# SCH-HC15C_REV2_PG3.net
KiCad netlist of a schematic drawn in Altium Designer
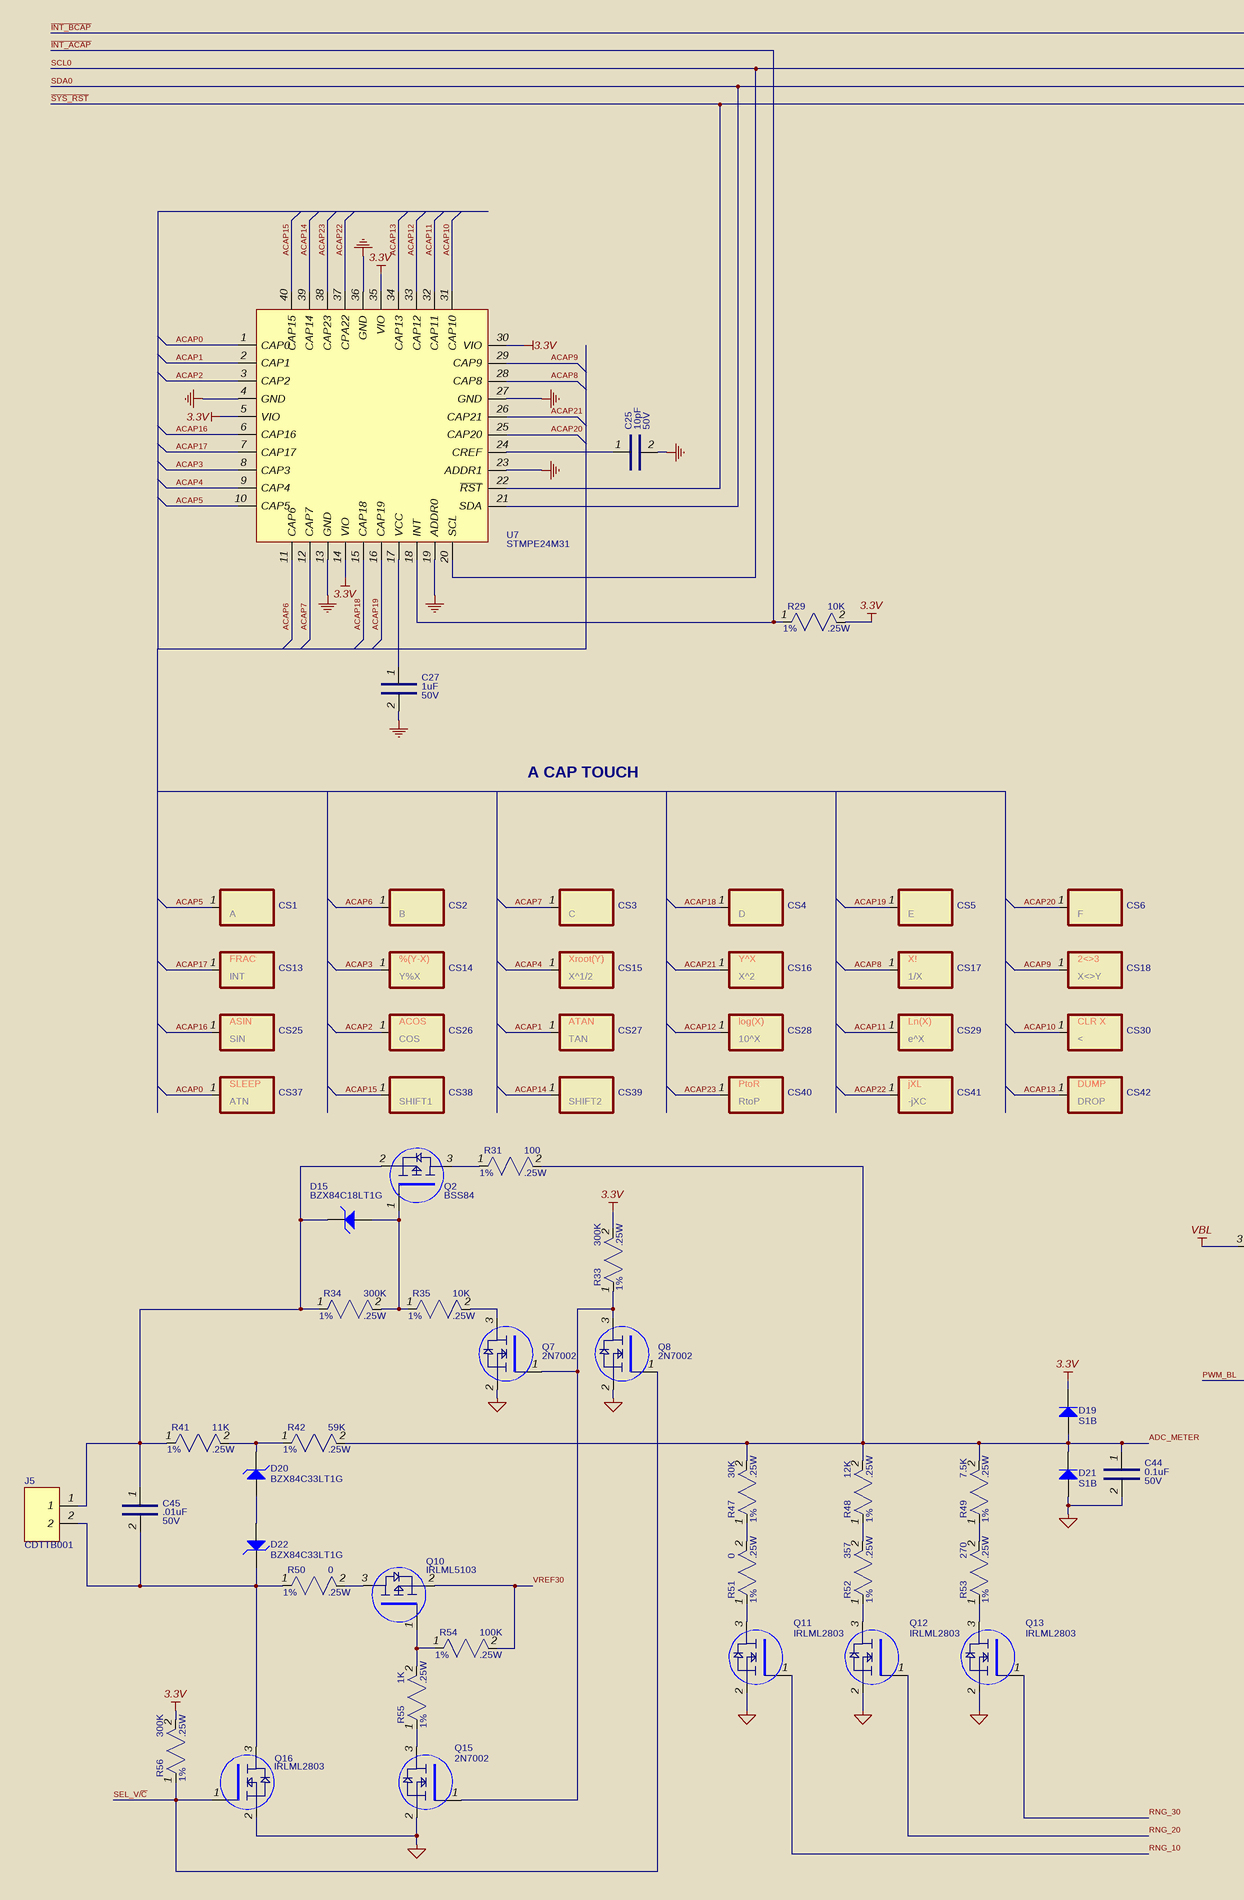
[diagram p0: SCH-HC15C_REV2_PG3.SchDoc, left]
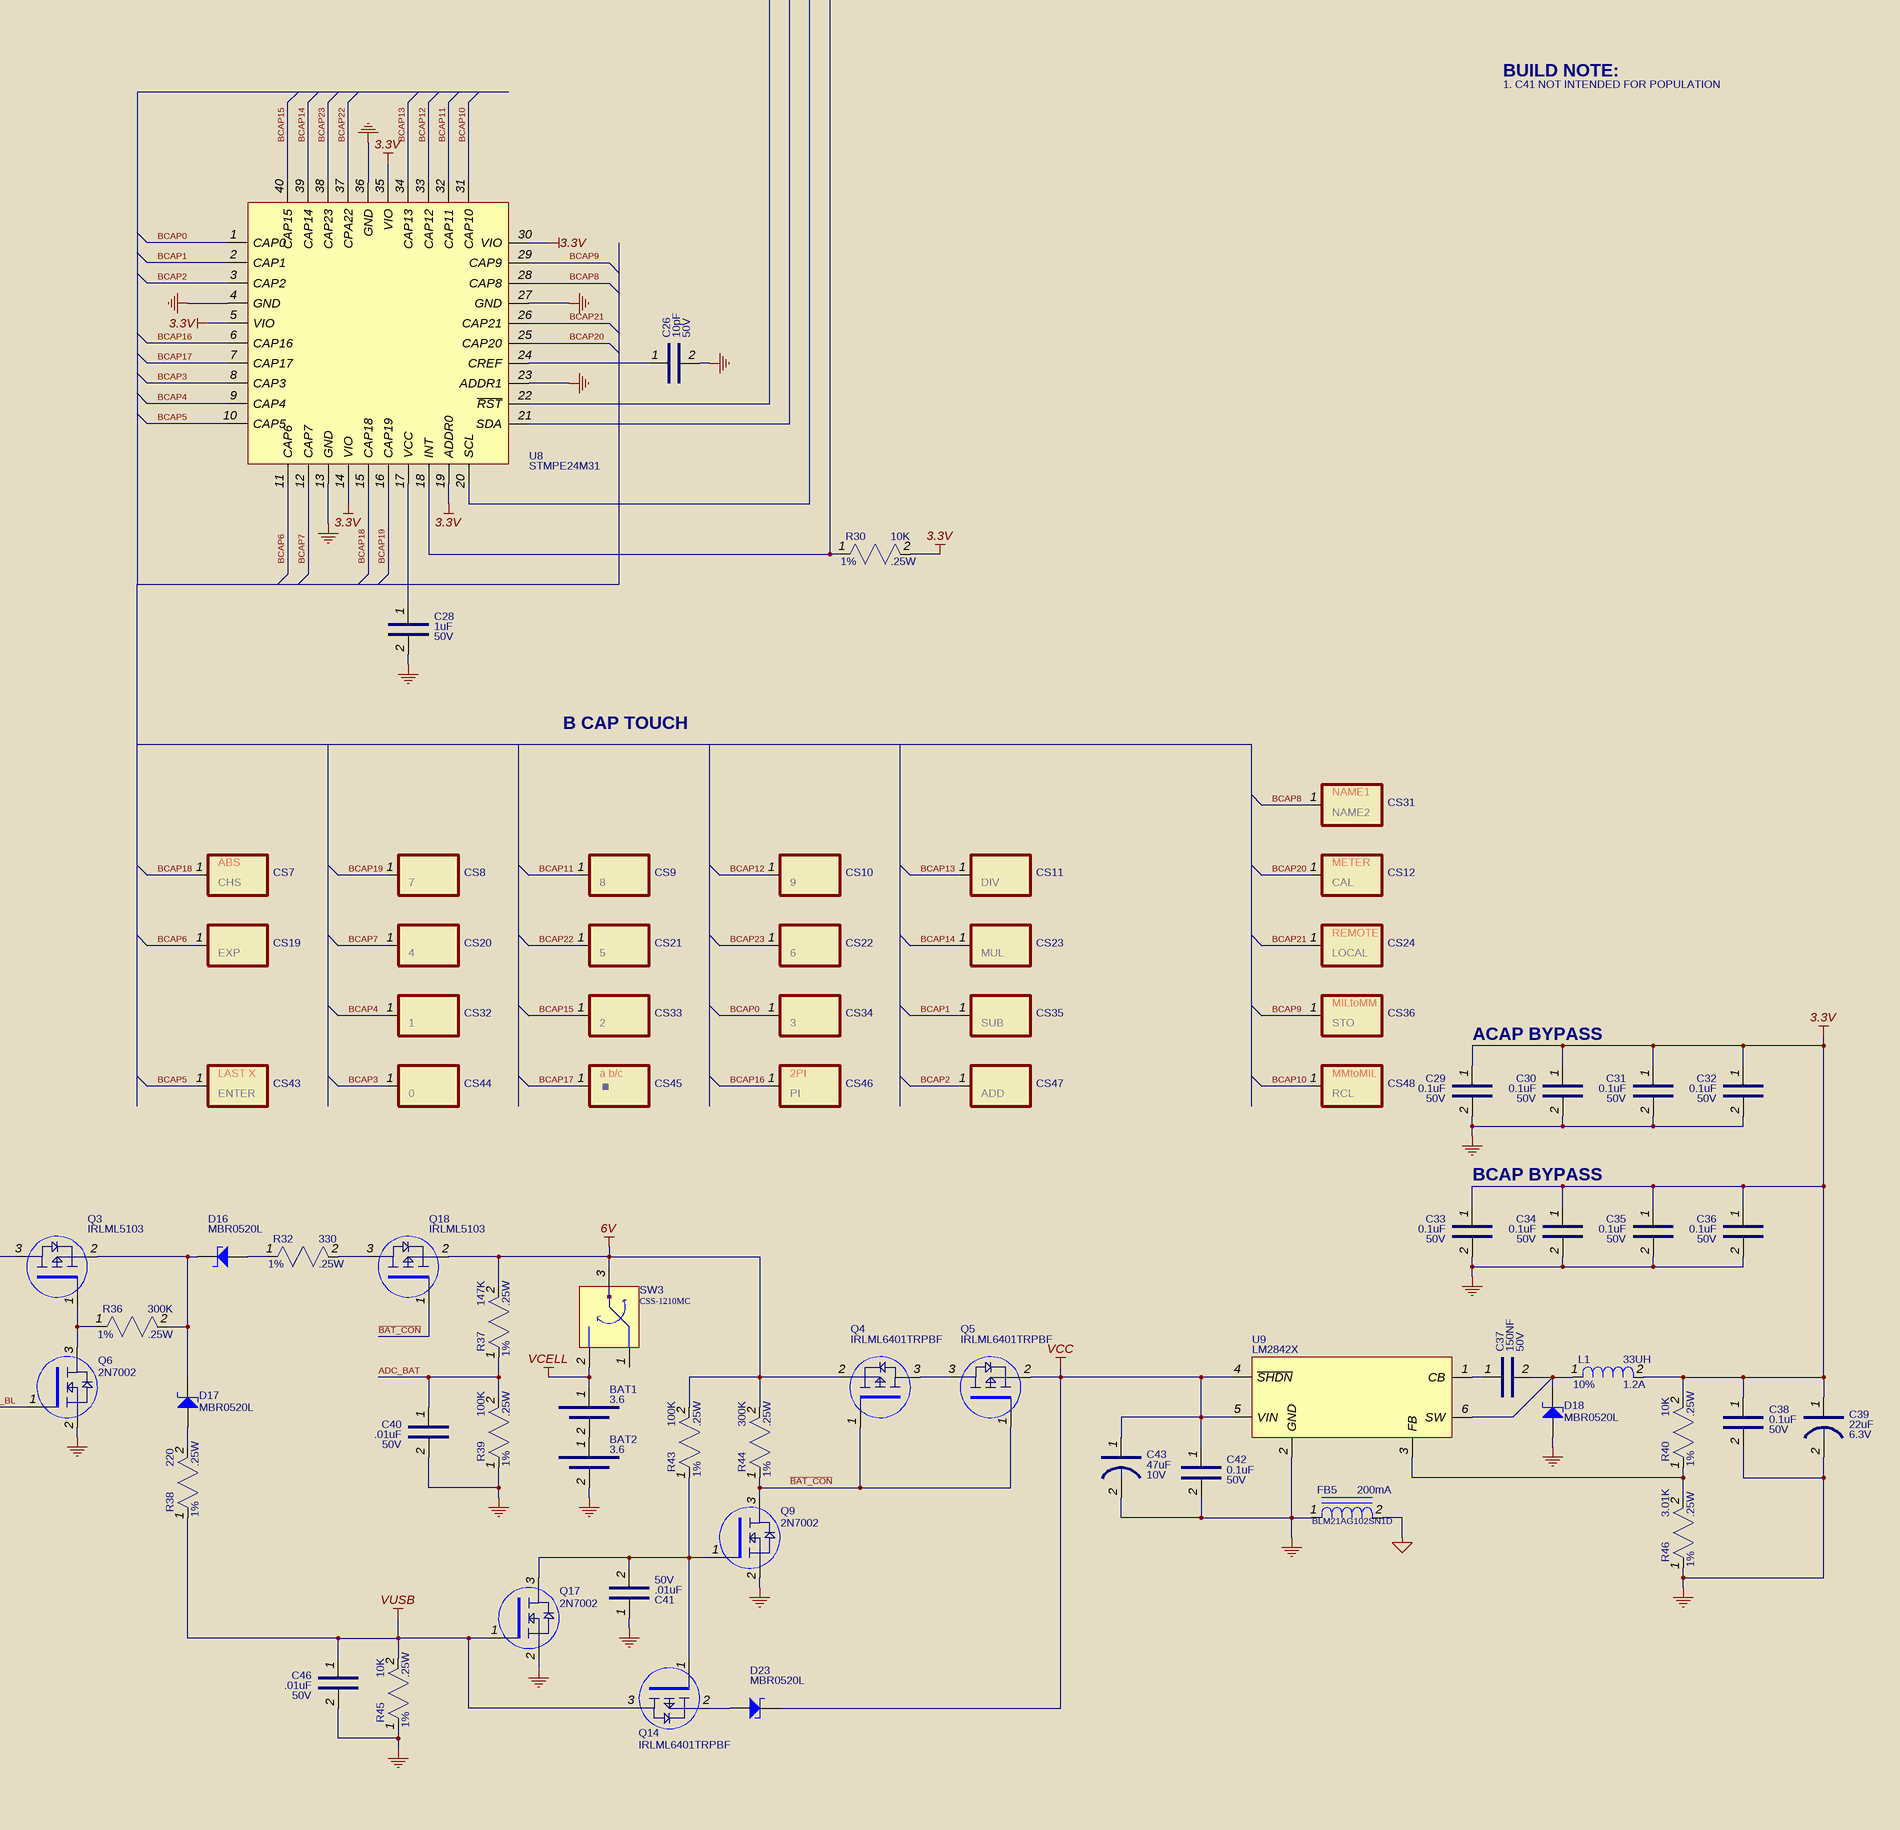
[diagram p1: SCH-HC15C_REV2_PG3.SchDoc, right]

(export (version "E")
  (design (tool "Eeschema 10.0.6"))
  (components
    (comp (ref "BAT1")
      (value "CDEVA00082_3")
      (footprint "KEYSTONE_108")
      (description "BAT HOLDER 1/2AA TH ROHS")
      (fields (field (name "MFG") "KEYSTONE") (field (name "VOLTAGE") "3.6"))
      (libsource (lib "HabLib") (part "CDEVA00082_3"))
    )
    (comp (ref "BAT2")
      (value "CDEVA00082_3")
      (footprint "KEYSTONE_108")
      (description "BAT HOLDER 1/2AA TH ROHS")
      (fields (field (name "MFG") "KEYSTONE") (field (name "VOLTAGE") "3.6"))
      (libsource (lib "HabLib") (part "CDEVA00082_3"))
    )
    (comp (ref "C25")
      (value "10pF")
      (footprint "3216[1206] - TAN COLOR")
      (description "CAP, CERAMIC, NPO, 10PF, 50V, 1206, 5%, RoHS")
      (fields (field (name "MFG") "AVX") (field (name "TOLERANCE") "10%") (field (name "VOLTAGE") "50V"))
      (libsource (lib "HabLib") (part "CDECA00143"))
    )
    (comp (ref "C26")
      (value "10pF")
      (footprint "3216[1206] - TAN COLOR")
      (description "CAP, CERAMIC, NPO, 10PF, 50V, 1206, 5%, RoHS")
      (fields (field (name "MFG") "AVX") (field (name "TOLERANCE") "10%") (field (name "VOLTAGE") "50V"))
      (libsource (lib "HabLib") (part "CDECA00143"))
    )
    (comp (ref "C27")
      (value "1uF")
      (footprint "3225[1210]")
      (description "CAP, CERAMIC CHIP 1UF 10% 50V X7R ROHS")
      (fields (field (name "MFG") "AVX") (field (name "TOLERANCE") "10%") (field (name "VOLTAGE") "50V"))
      (libsource (lib "HabLib") (part "CDECA00122"))
    )
    (comp (ref "C28")
      (value "1uF")
      (footprint "3225[1210]")
      (description "CAP, CERAMIC CHIP 1UF 10% 50V X7R ROHS")
      (fields (field (name "MFG") "AVX") (field (name "TOLERANCE") "10%") (field (name "VOLTAGE") "50V"))
      (libsource (lib "HabLib") (part "CDECA00122"))
    )
    (comp (ref "C29")
      (value "0.1uF")
      (footprint "3216[1206] - TAN COLOR")
      (description "CAP, CERAMIC CHIP 0.1UF 10% 50V X7R ROHS")
      (fields (field (name "MFG") "AVX") (field (name "TOLERANCE") "10%") (field (name "VOLTAGE") "50V"))
      (libsource (lib "HabLib") (part "CDECA00070"))
    )
    (comp (ref "C30")
      (value "0.1uF")
      (footprint "3216[1206] - TAN COLOR")
      (description "CAP, CERAMIC CHIP 0.1UF 10% 50V X7R ROHS")
      (fields (field (name "MFG") "AVX") (field (name "TOLERANCE") "10%") (field (name "VOLTAGE") "50V"))
      (libsource (lib "HabLib") (part "CDECA00070"))
    )
    (comp (ref "C31")
      (value "0.1uF")
      (footprint "3216[1206] - TAN COLOR")
      (description "CAP, CERAMIC CHIP 0.1UF 10% 50V X7R ROHS")
      (fields (field (name "MFG") "AVX") (field (name "TOLERANCE") "10%") (field (name "VOLTAGE") "50V"))
      (libsource (lib "HabLib") (part "CDECA00070"))
    )
    (comp (ref "C32")
      (value "0.1uF")
      (footprint "3216[1206] - TAN COLOR")
      (description "CAP, CERAMIC CHIP 0.1UF 10% 50V X7R ROHS")
      (fields (field (name "MFG") "AVX") (field (name "TOLERANCE") "10%") (field (name "VOLTAGE") "50V"))
      (libsource (lib "HabLib") (part "CDECA00070"))
    )
    (comp (ref "C33")
      (value "0.1uF")
      (footprint "3216[1206] - TAN COLOR")
      (description "CAP, CERAMIC CHIP 0.1UF 10% 50V X7R ROHS")
      (fields (field (name "MFG") "AVX") (field (name "TOLERANCE") "10%") (field (name "VOLTAGE") "50V"))
      (libsource (lib "HabLib") (part "CDECA00070"))
    )
    (comp (ref "C34")
      (value "0.1uF")
      (footprint "3216[1206] - TAN COLOR")
      (description "CAP, CERAMIC CHIP 0.1UF 10% 50V X7R ROHS")
      (fields (field (name "MFG") "AVX") (field (name "TOLERANCE") "10%") (field (name "VOLTAGE") "50V"))
      (libsource (lib "HabLib") (part "CDECA00070"))
    )
    (comp (ref "C35")
      (value "0.1uF")
      (footprint "3216[1206] - TAN COLOR")
      (description "CAP, CERAMIC CHIP 0.1UF 10% 50V X7R ROHS")
      (fields (field (name "MFG") "AVX") (field (name "TOLERANCE") "10%") (field (name "VOLTAGE") "50V"))
      (libsource (lib "HabLib") (part "CDECA00070"))
    )
    (comp (ref "C36")
      (value "0.1uF")
      (footprint "3216[1206] - TAN COLOR")
      (description "CAP, CERAMIC CHIP 0.1UF 10% 50V X7R ROHS")
      (fields (field (name "MFG") "AVX") (field (name "TOLERANCE") "10%") (field (name "VOLTAGE") "50V"))
      (libsource (lib "HabLib") (part "CDECA00070"))
    )
    (comp (ref "C37")
      (value "150NF")
      (footprint "3216[1206] - TAN COLOR")
      (description "CAP, CERAMIC, X7R, 150NF, 50V, 1206, 10%, RoHS")
      (fields (field (name "MFG") "KEMET") (field (name "TOLERANCE") "10%") (field (name "VOLTAGE") "50V"))
      (libsource (lib "HabLib") (part "CDECA00143_1"))
    )
    (comp (ref "C38")
      (value "0.1uF")
      (footprint "3216[1206] - TAN COLOR")
      (description "CAP, CERAMIC CHIP 0.1UF 10% 50V X7R ROHS")
      (fields (field (name "MFG") "AVX") (field (name "TOLERANCE") "10%") (field (name "VOLTAGE") "50V"))
      (libsource (lib "HabLib") (part "CDECA00070"))
    )
    (comp (ref "C39")
      (value "22uF")
      (footprint "3216[1206] - TANTALUM")
      (description "CAP, TANT, 22UF, 6.3V, 20%, LOW ESR, 1206ROHS")
      (fields (field (name "MFG") "AVX") (field (name "TOLERANCE") "20%") (field (name "VOLTAGE") "6.3V"))
      (libsource (lib "HabLib") (part "CDECA00139_1"))
    )
    (comp (ref "C40")
      (value ".01uF")
      (footprint "3216[1206] - TAN COLOR")
      (description "CAP, CERAMIC CHIP 0.01UF 10% 50V X7R ROHS")
      (fields
        (field (name "MFG") "PANASONIC")
        (field (name "TOLERANCE") "10%")
        (field (name "VOLTAGE") "50V")
      )
      (libsource (lib "HabLib") (part "CDECA00085"))
    )
    (comp (ref "C41")
      (value ".01uF")
      (footprint "3216[1206] - TAN COLOR")
      (description "CAP, CERAMIC CHIP 0.01UF 10% 50V X7R ROHS")
      (fields
        (field (name "MFG") "PANASONIC")
        (field (name "TOLERANCE") "10%")
        (field (name "VOLTAGE") "50V")
      )
      (libsource (lib "HabLib") (part "CDECA00085"))
    )
    (comp (ref "C42")
      (value "0.1uF")
      (footprint "3216[1206] - TAN COLOR")
      (description "CAP, CERAMIC CHIP 0.1UF 10% 50V X7R ROHS")
      (fields (field (name "MFG") "AVX") (field (name "TOLERANCE") "10%") (field (name "VOLTAGE") "50V"))
      (libsource (lib "HabLib") (part "CDECA00070"))
    )
    (comp (ref "C43")
      (value "47uF")
      (footprint "CAP_TANT_3528")
      (description "CAP, TANT, 47UF, 25V, 20%, 3528 ROHS")
      (fields (field (name "MFG") "AVX") (field (name "TOLERANCE") "20%") (field (name "VOLTAGE") "10V"))
      (libsource (lib "HabLib") (part "CDECA00110_1"))
    )
    (comp (ref "C44")
      (value "0.1uF")
      (footprint "3216[1206] - TAN COLOR")
      (description "CAP, CERAMIC CHIP 0.1UF 10% 50V X7R ROHS")
      (fields (field (name "MFG") "AVX") (field (name "TOLERANCE") "10%") (field (name "VOLTAGE") "50V"))
      (libsource (lib "HabLib") (part "CDECA00070"))
    )
    (comp (ref "C45")
      (value ".01uF")
      (footprint "3216[1206] - TAN COLOR")
      (description "CAP, CERAMIC CHIP 0.01UF 10% 50V X7R ROHS")
      (fields
        (field (name "MFG") "PANASONIC")
        (field (name "TOLERANCE") "10%")
        (field (name "VOLTAGE") "50V")
      )
      (libsource (lib "") (part "CDECA00085_1"))
    )
    (comp (ref "C46")
      (value ".01uF")
      (footprint "3216[1206] - TAN COLOR")
      (description "CAP, CERAMIC CHIP 0.01UF 10% 50V X7R ROHS")
      (fields
        (field (name "MFG") "PANASONIC")
        (field (name "TOLERANCE") "10%")
        (field (name "VOLTAGE") "50V")
      )
      (libsource (lib "HabLib") (part "CDECA00085"))
    )
    (comp (ref "CS1")
      (value "CAP_SENSOR")
      (footprint "CAPTOUCH1_10X10")
      (description "CAP SENSOR FOR PCB")
      (fields (field (name "VALUE2") "A") (field (name "PUBLISHER") "Altium Limited"))
      (libsource (lib "HabLib") (part "CAP_SENSOR"))
    )
    (comp (ref "CS2")
      (value "CAP_SENSOR")
      (footprint "CAPTOUCH1_10X10")
      (description "CAP SENSOR FOR PCB")
      (fields (field (name "VALUE2") "B") (field (name "PUBLISHER") "Altium Limited"))
      (libsource (lib "HabLib") (part "CAP_SENSOR"))
    )
    (comp (ref "CS3")
      (value "CAP_SENSOR")
      (footprint "CAPTOUCH1_10X10")
      (description "CAP SENSOR FOR PCB")
      (fields (field (name "VALUE2") "C") (field (name "PUBLISHER") "Altium Limited"))
      (libsource (lib "HabLib") (part "CAP_SENSOR"))
    )
    (comp (ref "CS4")
      (value "CAP_SENSOR")
      (footprint "CAPTOUCH1_10X10")
      (description "CAP SENSOR FOR PCB")
      (fields (field (name "VALUE2") "D") (field (name "PUBLISHER") "Altium Limited"))
      (libsource (lib "HabLib") (part "CAP_SENSOR"))
    )
    (comp (ref "CS5")
      (value "CAP_SENSOR")
      (footprint "CAPTOUCH1_10X10")
      (description "CAP SENSOR FOR PCB")
      (fields (field (name "VALUE2") "E") (field (name "PUBLISHER") "Altium Limited"))
      (libsource (lib "HabLib") (part "CAP_SENSOR"))
    )
    (comp (ref "CS6")
      (value "CAP_SENSOR")
      (footprint "CAPTOUCH1_10X10")
      (description "CAP SENSOR FOR PCB")
      (fields (field (name "VALUE2") "F") (field (name "PUBLISHER") "Altium Limited"))
      (libsource (lib "HabLib") (part "CAP_SENSOR"))
    )
    (comp (ref "CS7")
      (value "ABS")
      (footprint "CAPTOUCH1_10X10")
      (description "CAP SENSOR FOR PCB")
      (fields
        (field (name "VALUE2") "CHS")
        (field (name "Comment") "CAP_SENSOR")
        (field (name "PUBLISHER") "Altium Limited")
      )
      (libsource (lib "HabLib") (part "CAP_SENSOR"))
    )
    (comp (ref "CS8")
      (value "CAP_SENSOR")
      (footprint "CAPTOUCH1_10X10")
      (description "CAP SENSOR FOR PCB")
      (fields (field (name "VALUE2") "7") (field (name "PUBLISHER") "Altium Limited"))
      (libsource (lib "HabLib") (part "CAP_SENSOR"))
    )
    (comp (ref "CS9")
      (value "CAP_SENSOR")
      (footprint "CAPTOUCH1_10X10")
      (description "CAP SENSOR FOR PCB")
      (fields (field (name "VALUE2") "8") (field (name "PUBLISHER") "Altium Limited"))
      (libsource (lib "HabLib") (part "CAP_SENSOR"))
    )
    (comp (ref "CS10")
      (value "CAP_SENSOR")
      (footprint "CAPTOUCH1_10X10")
      (description "CAP SENSOR FOR PCB")
      (fields (field (name "VALUE2") "9") (field (name "PUBLISHER") "Altium Limited"))
      (libsource (lib "HabLib") (part "CAP_SENSOR"))
    )
    (comp (ref "CS11")
      (value "CAP_SENSOR")
      (footprint "CAPTOUCH1_10X10")
      (description "CAP SENSOR FOR PCB")
      (fields (field (name "VALUE2") "DIV") (field (name "PUBLISHER") "Altium Limited"))
      (libsource (lib "HabLib") (part "CAP_SENSOR"))
    )
    (comp (ref "CS12")
      (value "METER")
      (footprint "CAPTOUCH1_10X10")
      (description "CAP SENSOR FOR PCB")
      (fields
        (field (name "VALUE2") "CAL")
        (field (name "Comment") "CAP_SENSOR")
        (field (name "PUBLISHER") "Altium Limited")
      )
      (libsource (lib "HabLib") (part "CAP_SENSOR"))
    )
    (comp (ref "CS13")
      (value "FRAC")
      (footprint "CAPTOUCH1_10X10")
      (description "CAP SENSOR FOR PCB")
      (fields
        (field (name "VALUE2") "INT")
        (field (name "Comment") "CAP_SENSOR")
        (field (name "PUBLISHER") "Altium Limited")
      )
      (libsource (lib "HabLib") (part "CAP_SENSOR"))
    )
    (comp (ref "CS14")
      (value "%(Y-X)")
      (footprint "CAPTOUCH1_10X10")
      (description "CAP SENSOR FOR PCB")
      (fields
        (field (name "VALUE2") "Y%X")
        (field (name "Comment") "CAP_SENSOR")
        (field (name "PUBLISHER") "Altium Limited")
      )
      (libsource (lib "HabLib") (part "CAP_SENSOR"))
    )
    (comp (ref "CS15")
      (value "Xroot(Y)")
      (footprint "CAPTOUCH1_10X10")
      (description "CAP SENSOR FOR PCB")
      (fields
        (field (name "VALUE2") "X^1/2")
        (field (name "Comment") "CAP_SENSOR")
        (field (name "PUBLISHER") "Altium Limited")
      )
      (libsource (lib "HabLib") (part "CAP_SENSOR"))
    )
    (comp (ref "CS16")
      (value "Y^X")
      (footprint "CAPTOUCH1_10X10")
      (description "CAP SENSOR FOR PCB")
      (fields
        (field (name "VALUE2") "X^2")
        (field (name "Comment") "CAP_SENSOR")
        (field (name "PUBLISHER") "Altium Limited")
      )
      (libsource (lib "HabLib") (part "CAP_SENSOR"))
    )
    (comp (ref "CS17")
      (value "X!")
      (footprint "CAPTOUCH1_10X10")
      (description "CAP SENSOR FOR PCB")
      (fields
        (field (name "VALUE2") "1/X")
        (field (name "Comment") "CAP_SENSOR")
        (field (name "PUBLISHER") "Altium Limited")
      )
      (libsource (lib "HabLib") (part "CAP_SENSOR"))
    )
    (comp (ref "CS18")
      (value "2<>3")
      (footprint "CAPTOUCH1_10X10")
      (description "CAP SENSOR FOR PCB")
      (fields
        (field (name "VALUE2") "X<>Y")
        (field (name "Comment") "CAP_SENSOR")
        (field (name "PUBLISHER") "Altium Limited")
      )
      (libsource (lib "HabLib") (part "CAP_SENSOR"))
    )
    (comp (ref "CS19")
      (value "CAP_SENSOR")
      (footprint "CAPTOUCH1_10X10")
      (description "CAP SENSOR FOR PCB")
      (fields (field (name "VALUE2") "EXP") (field (name "PUBLISHER") "Altium Limited"))
      (libsource (lib "HabLib") (part "CAP_SENSOR"))
    )
    (comp (ref "CS20")
      (value "CAP_SENSOR")
      (footprint "CAPTOUCH1_10X10")
      (description "CAP SENSOR FOR PCB")
      (fields (field (name "VALUE2") "4") (field (name "PUBLISHER") "Altium Limited"))
      (libsource (lib "HabLib") (part "CAP_SENSOR"))
    )
    (comp (ref "CS21")
      (value "CAP_SENSOR")
      (footprint "CAPTOUCH1_10X10")
      (description "CAP SENSOR FOR PCB")
      (fields (field (name "VALUE2") "5") (field (name "PUBLISHER") "Altium Limited"))
      (libsource (lib "HabLib") (part "CAP_SENSOR"))
    )
    (comp (ref "CS22")
      (value "CAP_SENSOR")
      (footprint "CAPTOUCH1_10X10")
      (description "CAP SENSOR FOR PCB")
      (fields (field (name "VALUE2") "6") (field (name "PUBLISHER") "Altium Limited"))
      (libsource (lib "HabLib") (part "CAP_SENSOR"))
    )
    (comp (ref "CS23")
      (value "CAP_SENSOR")
      (footprint "CAPTOUCH1_10X10")
      (description "CAP SENSOR FOR PCB")
      (fields (field (name "VALUE2") "MUL") (field (name "PUBLISHER") "Altium Limited"))
      (libsource (lib "HabLib") (part "CAP_SENSOR"))
    )
    (comp (ref "CS24")
      (value "REMOTE")
      (footprint "CAPTOUCH1_10X10")
      (description "CAP SENSOR FOR PCB")
      (fields
        (field (name "VALUE2") "LOCAL")
        (field (name "Comment") "CAP_SENSOR")
        (field (name "PUBLISHER") "Altium Limited")
      )
      (libsource (lib "HabLib") (part "CAP_SENSOR"))
    )
    (comp (ref "CS25")
      (value "ASIN")
      (footprint "CAPTOUCH1_10X10")
      (description "CAP SENSOR FOR PCB")
      (fields
        (field (name "VALUE2") "SIN")
        (field (name "Comment") "CAP_SENSOR")
        (field (name "PUBLISHER") "Altium Limited")
      )
      (libsource (lib "HabLib") (part "CAP_SENSOR"))
    )
    (comp (ref "CS26")
      (value "ACOS")
      (footprint "CAPTOUCH1_10X10")
      (description "CAP SENSOR FOR PCB")
      (fields
        (field (name "VALUE2") "COS")
        (field (name "Comment") "CAP_SENSOR")
        (field (name "PUBLISHER") "Altium Limited")
      )
      (libsource (lib "HabLib") (part "CAP_SENSOR"))
    )
    (comp (ref "CS27")
      (value "ATAN")
      (footprint "CAPTOUCH1_10X10")
      (description "CAP SENSOR FOR PCB")
      (fields
        (field (name "VALUE2") "TAN")
        (field (name "Comment") "CAP_SENSOR")
        (field (name "PUBLISHER") "Altium Limited")
      )
      (libsource (lib "HabLib") (part "CAP_SENSOR"))
    )
    (comp (ref "CS28")
      (value "log(X)")
      (footprint "CAPTOUCH1_10X10")
      (description "CAP SENSOR FOR PCB")
      (fields
        (field (name "VALUE2") "10^X")
        (field (name "Comment") "CAP_SENSOR")
        (field (name "PUBLISHER") "Altium Limited")
      )
      (libsource (lib "HabLib") (part "CAP_SENSOR"))
    )
    (comp (ref "CS29")
      (value "Ln(X)")
      (footprint "CAPTOUCH1_10X10")
      (description "CAP SENSOR FOR PCB")
      (fields
        (field (name "VALUE2") "e^X")
        (field (name "Comment") "CAP_SENSOR")
        (field (name "PUBLISHER") "Altium Limited")
      )
      (libsource (lib "HabLib") (part "CAP_SENSOR"))
    )
    (comp (ref "CS30")
      (value "CLR X")
      (footprint "CAPTOUCH1_10X10")
      (description "CAP SENSOR FOR PCB")
      (fields
        (field (name "VALUE2") "<")
        (field (name "Comment") "CAP_SENSOR")
        (field (name "PUBLISHER") "Altium Limited")
      )
      (libsource (lib "HabLib") (part "CAP_SENSOR"))
    )
    (comp (ref "CS31")
      (value "NAME1")
      (footprint "CAPTOUCH1_10X10")
      (description "CAP SENSOR FOR PCB")
      (fields
        (field (name "VALUE2") "NAME2")
        (field (name "Comment") "CAP_SENSOR")
        (field (name "PUBLISHER") "Altium Limited")
      )
      (libsource (lib "HabLib") (part "CAP_SENSOR"))
    )
    (comp (ref "CS32")
      (value "CAP_SENSOR")
      (footprint "CAPTOUCH1_10X10")
      (description "CAP SENSOR FOR PCB")
      (fields (field (name "VALUE2") "1") (field (name "PUBLISHER") "Altium Limited"))
      (libsource (lib "HabLib") (part "CAP_SENSOR"))
    )
    (comp (ref "CS33")
      (value "CAP_SENSOR")
      (footprint "CAPTOUCH1_10X10")
      (description "CAP SENSOR FOR PCB")
      (fields (field (name "VALUE2") "2") (field (name "PUBLISHER") "Altium Limited"))
      (libsource (lib "HabLib") (part "CAP_SENSOR"))
    )
    (comp (ref "CS34")
      (value "CAP_SENSOR")
      (footprint "CAPTOUCH1_10X10")
      (description "CAP SENSOR FOR PCB")
      (fields (field (name "VALUE2") "3") (field (name "PUBLISHER") "Altium Limited"))
      (libsource (lib "HabLib") (part "CAP_SENSOR"))
    )
    (comp (ref "CS35")
      (value "CAP_SENSOR")
      (footprint "CAPTOUCH1_10X10")
      (description "CAP SENSOR FOR PCB")
      (fields (field (name "VALUE2") "SUB") (field (name "PUBLISHER") "Altium Limited"))
      (libsource (lib "HabLib") (part "CAP_SENSOR"))
    )
    (comp (ref "CS36")
      (value "MILtoMM")
      (footprint "CAPTOUCH1_10X10")
      (description "CAP SENSOR FOR PCB")
      (fields
        (field (name "VALUE2") "STO")
        (field (name "Comment") "CAP_SENSOR")
        (field (name "PUBLISHER") "Altium Limited")
      )
      (libsource (lib "HabLib") (part "CAP_SENSOR"))
    )
    (comp (ref "CS37")
      (value "SLEEP")
      (footprint "CAPTOUCH1_10X10")
      (description "CAP SENSOR FOR PCB")
      (fields
        (field (name "VALUE2") "ATN")
        (field (name "Comment") "CAP_SENSOR")
        (field (name "PUBLISHER") "Altium Limited")
      )
      (libsource (lib "HabLib") (part "CAP_SENSOR"))
    )
    (comp (ref "CS38")
      (value "CAP_SENSOR")
      (footprint "CAPTOUCH1_10X10")
      (description "CAP SENSOR FOR PCB")
      (fields (field (name "VALUE2") "SHIFT1") (field (name "PUBLISHER") "Altium Limited"))
      (libsource (lib "HabLib") (part "CAP_SENSOR"))
    )
    (comp (ref "CS39")
      (value "CAP_SENSOR")
      (footprint "CAPTOUCH1_10X10")
      (description "CAP SENSOR FOR PCB")
      (fields (field (name "VALUE2") "SHIFT2") (field (name "PUBLISHER") "Altium Limited"))
      (libsource (lib "HabLib") (part "CAP_SENSOR"))
    )
    (comp (ref "CS40")
      (value "PtoR")
      (footprint "CAPTOUCH1_10X10")
      (description "CAP SENSOR FOR PCB")
      (fields
        (field (name "VALUE2") "RtoP")
        (field (name "Comment") "CAP_SENSOR")
        (field (name "PUBLISHER") "Altium Limited")
      )
      (libsource (lib "HabLib") (part "CAP_SENSOR"))
    )
    (comp (ref "CS41")
      (value "jXL")
      (footprint "CAPTOUCH1_10X10")
      (description "CAP SENSOR FOR PCB")
      (fields
        (field (name "VALUE2") "-jXC")
        (field (name "Comment") "CAP_SENSOR")
        (field (name "PUBLISHER") "Altium Limited")
      )
      (libsource (lib "HabLib") (part "CAP_SENSOR"))
    )
    (comp (ref "CS42")
      (value "DUMP")
      (footprint "CAPTOUCH1_10X10")
      (description "CAP SENSOR FOR PCB")
      (fields
        (field (name "VALUE2") "DROP")
        (field (name "Comment") "CAP_SENSOR")
        (field (name "PUBLISHER") "Altium Limited")
      )
      (libsource (lib "HabLib") (part "CAP_SENSOR"))
    )
    (comp (ref "CS43")
      (value "LAST X")
      (footprint "CAPTOUCH1_10X23")
      (description "CAP SENSOR FOR PCB")
      (fields
        (field (name "VALUE2") "ENTER")
        (field (name "Comment") "CAP_SENSOR_ENT")
        (field (name "PUBLISHER") "Altium Limited")
      )
      (libsource (lib "HabLib") (part "CAP_SENSOR_ENT"))
    )
    (comp (ref "CS44")
      (value "CAP_SENSOR")
      (footprint "CAPTOUCH1_10X10")
      (description "CAP SENSOR FOR PCB")
      (fields (field (name "VALUE2") "0") (field (name "PUBLISHER") "Altium Limited"))
      (libsource (lib "HabLib") (part "CAP_SENSOR"))
    )
    (comp (ref "CS45")
      (value "a b/c")
      (footprint "CAPTOUCH1_10X10")
      (description "CAP SENSOR FOR PCB")
      (fields
        (field (name "VALUE2") ".")
        (field (name "Comment") "CAP_SENSOR")
        (field (name "PUBLISHER") "Altium Limited")
      )
      (libsource (lib "HabLib") (part "CAP_SENSOR"))
    )
    (comp (ref "CS46")
      (value "2PI")
      (footprint "CAPTOUCH1_10X10")
      (description "CAP SENSOR FOR PCB")
      (fields
        (field (name "VALUE2") "PI")
        (field (name "Comment") "CAP_SENSOR")
        (field (name "PUBLISHER") "Altium Limited")
      )
      (libsource (lib "HabLib") (part "CAP_SENSOR"))
    )
    (comp (ref "CS47")
      (value "CAP_SENSOR")
      (footprint "CAPTOUCH1_10X10")
      (description "CAP SENSOR FOR PCB")
      (fields (field (name "VALUE2") "ADD") (field (name "PUBLISHER") "Altium Limited"))
      (libsource (lib "HabLib") (part "CAP_SENSOR"))
    )
    (comp (ref "CS48")
      (value "MMtoMIL")
      (footprint "CAPTOUCH1_10X10")
      (description "CAP SENSOR FOR PCB")
      (fields
        (field (name "VALUE2") "RCL")
        (field (name "Comment") "CAP_SENSOR")
        (field (name "PUBLISHER") "Altium Limited")
      )
      (libsource (lib "HabLib") (part "CAP_SENSOR"))
    )
    (comp (ref "D15")
      (value "BZX84C18LT1G")
      (footprint "SOT23 - TRANSISTOR")
      (description "DIODE, ZENER, 18V, 225MW, SOT-23, ROHS")
      (fields (field (name "MFG") "ON SEMICONDUCTOR") (field (name "Comment") "CDEDA00055_1"))
      (libsource (lib "HabLib") (part "CDEDA00055_1"))
    )
    (comp (ref "D16")
      (value "MBR0520L")
      (footprint "SOD123")
      (description "Diode, Schottky rectifier, 20V, 0.5A, SOD-123 package, Pb free")
      (fields (field (name "MFG") "FAIRCHILD SEMI") (field (name "Comment") "CDEDA00019_1"))
      (libsource (lib "HabLib") (part "CDEDA00019_1"))
    )
    (comp (ref "D17")
      (value "MBR0520L")
      (footprint "SOD123")
      (description "Diode, Schottky rectifier, 20V, 0.5A, SOD-123 package, Pb free")
      (fields (field (name "MFG") "FAIRCHILD SEMI") (field (name "Comment") "CDEDA00019_1"))
      (libsource (lib "HabLib") (part "CDEDA00019_1"))
    )
    (comp (ref "D18")
      (value "MBR0520L")
      (footprint "SOD123")
      (description "Diode, Schottky rectifier, 20V, 0.5A, SOD-123 package, Pb free")
      (fields (field (name "MFG") "FAIRCHILD SEMI") (field (name "Comment") "CDEDA00019_1"))
      (libsource (lib "HabLib") (part "CDEDA00019_1"))
    )
    (comp (ref "D19")
      (value "S1B")
      (footprint "DIODE SMA")
      (description "DIODE, 1A, 100V, SMA, ROHS")
      (fields (field (name "MFG") "FAIRCHILD SEMICONDUCTOR") (field (name "Comment") "CDEDA00055_3"))
      (libsource (lib "HabLib") (part "CDEDA00055_3"))
    )
    (comp (ref "D20")
      (value "BZX84C33LT1G")
      (footprint "SOT23 - TRANSISTOR")
      (description "DIODE, ZENER, 33V, 225MW, SOT-23, ROHS")
      (fields (field (name "MFG") "ON SEMICONDUCTOR") (field (name "Comment") "CDEDA00055_2"))
      (libsource (lib "HabLib") (part "CDEDA00055_2"))
    )
    (comp (ref "D21")
      (value "S1B")
      (footprint "DIODE SMA")
      (description "DIODE, 1A, 100V, SMA, ROHS")
      (fields (field (name "MFG") "FAIRCHILD SEMICONDUCTOR") (field (name "Comment") "CDEDA00055_3"))
      (libsource (lib "HabLib") (part "CDEDA00055_3"))
    )
    (comp (ref "D22")
      (value "BZX84C33LT1G")
      (footprint "SOT23 - TRANSISTOR")
      (description "DIODE, ZENER, 33V, 225MW, SOT-23, ROHS")
      (fields (field (name "MFG") "ON SEMICONDUCTOR") (field (name "Comment") "CDEDA00055_2"))
      (libsource (lib "HabLib") (part "CDEDA00055_2"))
    )
    (comp (ref "D23")
      (value "MBR0520L")
      (footprint "SOD123")
      (description "Diode, Schottky rectifier, 20V, 0.5A, SOD-123 package, Pb free")
      (fields (field (name "MFG") "FAIRCHILD SEMI") (field (name "Comment") "CDEDA00019_1"))
      (libsource (lib "HabLib") (part "CDEDA00019_1"))
    )
    (comp (ref "FB5")
      (value "CDEVA00115")
      (footprint "2012[0805]")
      (description "FERRITE, 1KOHM AT 100MHZ, 220MA, .450DCR")
      (fields
        (field (name "MFG") "MURATA")
        (field (name "TOLERANCE") "10%")
        (field (name "MFG_PN") "BLM21AG102SN1D")
        (field (name "POWER") "200mA")
        (field (name "PUBLISHER") "Altium Limited")
      )
      (libsource (lib "HabLib") (part "CDEVA00115"))
    )
    (comp (ref "J5")
      (value "CDTTB001")
      (footprint "PHOENIX_CONTACT_1933189")
      (description "CONN, HDR, 2PIN, 5MM PHONIX CONTACT, ROHS")
      (fields (field (name "MFG") "PHOENIX CONTACT"))
      (libsource (lib "HabLib") (part "CDTTB001"))
    )
    (comp (ref "L1")
      (value "33UH")
      (footprint "BOURNS_SDR0805-XXXX")
      (description "INDUCTOR, 33UH, 10%, SMT, NON-SHIELDED, FERRITE CORE, ROHS")
      (fields
        (field (name "MFG") "BOURNS")
        (field (name "TOLERANCE") "10%")
        (field (name "POWER") "1.2A")
        (field (name "Comment") "CDEHA00005_1")
      )
      (libsource (lib "HabLib") (part "CDEHA00005_1"))
    )
    (comp (ref "Q2")
      (value "BSS84")
      (footprint "SOT23 - TRANSISTOR")
      (description "MOSFET P CHN, VDS=50V, RDSON = 10OHM, SOT 23")
      (fields
        (field (name "MFG") "DIODES INC")
        (field (name "Comment") "CDENA00031_1")
        (field (name "PUBLISHER") "Altium Limited")
      )
      (libsource (lib "HabLib") (part "CDENA00031_1"))
    )
    (comp (ref "Q3")
      (value "IRLML5103")
      (footprint "SOT23 - TRANSISTOR")
      (description "MOSFET P CHN, VDS=30V, RDSON = .6OHM, SOT 23")
      (fields
        (field (name "MFG") "INTERNATIONAL RECTIFIER")
        (field (name "Comment") "CDENA00031")
        (field (name "PUBLISHER") "Altium Limited")
      )
      (libsource (lib "HabLib") (part "CDENA00031"))
    )
    (comp (ref "Q4")
      (value "IRLML6401TRPBF")
      (footprint "SOT23 - TRANSISTOR")
      (description "MOSFET P CHN, VDS=12V, RDSON = .05OHM, SOT 23")
      (fields
        (field (name "MFG") "INTERNATIONAL RECTIFIER")
        (field (name "Comment") "CDENA00031_3")
        (field (name "PUBLISHER") "Altium Limited")
      )
      (libsource (lib "") (part "CDENA00031_3_1"))
    )
    (comp (ref "Q5")
      (value "IRLML6401TRPBF")
      (footprint "SOT23 - TRANSISTOR")
      (description "MOSFET P CHN, VDS=12V, RDSON = .05OHM, SOT 23")
      (fields
        (field (name "MFG") "INTERNATIONAL RECTIFIER")
        (field (name "Comment") "CDENA00031_3")
        (field (name "PUBLISHER") "Altium Limited")
      )
      (libsource (lib "HabLib") (part "CDENA00031_3"))
    )
    (comp (ref "Q6")
      (value "2N7002")
      (footprint "SOT23 - TRANSISTOR")
      (description "MOSFET N CHN, VDS=60V, 115 mA, SOT 23")
      (fields
        (field (name "MFG") "DIODES INC")
        (field (name "Comment") "CDENA00030")
        (field (name "PUBLISHER") "Altium Limited")
      )
      (libsource (lib "HabLib") (part "CDENA00030"))
    )
    (comp (ref "Q7")
      (value "2N7002")
      (footprint "SOT23 - TRANSISTOR")
      (description "MOSFET N CHN, VDS=60V, 115 mA, SOT 23")
      (fields
        (field (name "MFG") "DIODES INC")
        (field (name "Comment") "CDENA00030")
        (field (name "PUBLISHER") "Altium Limited")
      )
      (libsource (lib "") (part "CDENA00030_1"))
    )
    (comp (ref "Q8")
      (value "2N7002")
      (footprint "SOT23 - TRANSISTOR")
      (description "MOSFET N CHN, VDS=60V, 115 mA, SOT 23")
      (fields
        (field (name "MFG") "DIODES INC")
        (field (name "Comment") "CDENA00030")
        (field (name "PUBLISHER") "Altium Limited")
      )
      (libsource (lib "") (part "CDENA00030_1"))
    )
    (comp (ref "Q9")
      (value "2N7002")
      (footprint "SOT23 - TRANSISTOR")
      (description "MOSFET N CHN, VDS=60V, 115 mA, SOT 23")
      (fields
        (field (name "MFG") "DIODES INC")
        (field (name "Comment") "CDENA00030")
        (field (name "PUBLISHER") "Altium Limited")
      )
      (libsource (lib "HabLib") (part "CDENA00030"))
    )
    (comp (ref "Q10")
      (value "IRLML5103")
      (footprint "SOT23 - TRANSISTOR")
      (description "MOSFET P CHN, VDS=30V, RDSON = .6OHM, SOT 23")
      (fields
        (field (name "MFG") "INTERNATIONAL RECTIFIER")
        (field (name "Comment") "CDENA00031")
        (field (name "PUBLISHER") "Altium Limited")
      )
      (libsource (lib "HabLib") (part "CDENA00031"))
    )
    (comp (ref "Q11")
      (value "IRLML2803")
      (footprint "SOT23 - TRANSISTOR")
      (description "MOSFET N CHN, VDS=60V, 115 mA, SOT 23")
      (fields
        (field (name "MFG") "INTERNATIONAL RECTIFIER")
        (field (name "Comment") "CDENA00031_2")
        (field (name "PUBLISHER") "Altium Limited")
      )
      (libsource (lib "") (part "CDENA00031_2_1"))
    )
    (comp (ref "Q12")
      (value "IRLML2803")
      (footprint "SOT23 - TRANSISTOR")
      (description "MOSFET N CHN, VDS=60V, 115 mA, SOT 23")
      (fields
        (field (name "MFG") "INTERNATIONAL RECTIFIER")
        (field (name "Comment") "CDENA00031_2")
        (field (name "PUBLISHER") "Altium Limited")
      )
      (libsource (lib "") (part "CDENA00031_2_1"))
    )
    (comp (ref "Q13")
      (value "IRLML2803")
      (footprint "SOT23 - TRANSISTOR")
      (description "MOSFET N CHN, VDS=60V, 115 mA, SOT 23")
      (fields
        (field (name "MFG") "INTERNATIONAL RECTIFIER")
        (field (name "Comment") "CDENA00031_2")
        (field (name "PUBLISHER") "Altium Limited")
      )
      (libsource (lib "") (part "CDENA00031_2_1"))
    )
    (comp (ref "Q14")
      (value "IRLML6401TRPBF")
      (footprint "SOT23 - TRANSISTOR")
      (description "MOSFET P CHN, VDS=12V, RDSON = .05OHM, SOT 23")
      (fields
        (field (name "MFG") "INTERNATIONAL RECTIFIER")
        (field (name "Comment") "CDENA00031_3")
        (field (name "PUBLISHER") "Altium Limited")
      )
      (libsource (lib "") (part "CDENA00031_3_1"))
    )
    (comp (ref "Q15")
      (value "2N7002")
      (footprint "SOT23 - TRANSISTOR")
      (description "MOSFET N CHN, VDS=60V, 115 mA, SOT 23")
      (fields
        (field (name "MFG") "DIODES INC")
        (field (name "Comment") "CDENA00030")
        (field (name "PUBLISHER") "Altium Limited")
      )
      (libsource (lib "") (part "CDENA00030_1"))
    )
    (comp (ref "Q16")
      (value "IRLML2803")
      (footprint "SOT23 - TRANSISTOR")
      (description "MOSFET N CHN, VDS=60V, 115 mA, SOT 23")
      (fields
        (field (name "MFG") "INTERNATIONAL RECTIFIER")
        (field (name "Comment") "CDENA00031_2")
        (field (name "PUBLISHER") "Altium Limited")
      )
      (libsource (lib "HabLib") (part "CDENA00031_2"))
    )
    (comp (ref "Q17")
      (value "2N7002")
      (footprint "SOT23 - TRANSISTOR")
      (description "MOSFET N CHN, VDS=60V, 115 mA, SOT 23")
      (fields
        (field (name "MFG") "DIODES INC")
        (field (name "Comment") "CDENA00030")
        (field (name "PUBLISHER") "Altium Limited")
      )
      (libsource (lib "HabLib") (part "CDENA00030"))
    )
    (comp (ref "Q18")
      (value "IRLML5103")
      (footprint "SOT23 - TRANSISTOR")
      (description "MOSFET P CHN, VDS=30V, RDSON = .6OHM, SOT 23")
      (fields
        (field (name "MFG") "INTERNATIONAL RECTIFIER")
        (field (name "Comment") "CDENA00031")
        (field (name "PUBLISHER") "Altium Limited")
      )
      (libsource (lib "HabLib") (part "CDENA00031"))
    )
    (comp (ref "R29")
      (value "10K")
      (footprint "HabLib:3216[1206]")
      (description "RESISTOR, CHIP 1206 10K OHM 1% 1/4W THICK FILM ROHS")
      (fields
        (field (name "MFG") "PANASONIC")
        (field (name "TOLERANCE") "1%")
        (field (name "POWER") ".25W")
        (field (name "Comment") "CDERA00170")
        (field (name "PUBLISHER") "Altium Limited")
      )
      (libsource (lib "HabLib") (part "CDERA00170"))
    )
    (comp (ref "R30")
      (value "10K")
      (footprint "HabLib:3216[1206]")
      (description "RESISTOR, CHIP 1206 10K OHM 1% 1/4W THICK FILM ROHS")
      (fields
        (field (name "MFG") "PANASONIC")
        (field (name "TOLERANCE") "1%")
        (field (name "POWER") ".25W")
        (field (name "Comment") "CDERA00170")
        (field (name "PUBLISHER") "Altium Limited")
      )
      (libsource (lib "HabLib") (part "CDERA00170"))
    )
    (comp (ref "R31")
      (value "100")
      (footprint "HabLib:3216[1206]")
      (description "RESISTOR, CHIP 1206 100 OHM 1% 1/4W THICK FILM ROHS")
      (fields
        (field (name "MFG") "PANASONIC")
        (field (name "TOLERANCE") "1%")
        (field (name "POWER") ".25W")
        (field (name "Comment") "CDERA00176")
        (field (name "PUBLISHER") "Altium Limited")
      )
      (libsource (lib "HabLib") (part "CDERA00176"))
    )
    (comp (ref "R32")
      (value "330")
      (footprint "HABLIB:3216[1206]")
      (description "RESISTOR, CHIP 1206 330 OHM 1% 1/4W THICK FILM ROHS")
      (fields
        (field (name "MFG") "PANASONIC")
        (field (name "TOLERANCE") "1%")
        (field (name "POWER") ".25W")
        (field (name "Comment") "CDERA00154")
        (field (name "PUBLISHER") "Altium Limited")
      )
      (libsource (lib "HabLib") (part "CDERA00154"))
    )
    (comp (ref "R33")
      (value "300K")
      (footprint "HABLIB:3216[1206]")
      (description "RESISTOR, CHIP 1206 300K OHM 1% 1/4W THICK FILM ROHS")
      (fields
        (field (name "MFG") "PANASONIC")
        (field (name "TOLERANCE") "1%")
        (field (name "POWER") ".25W")
        (field (name "Comment") "CDERA00275_8")
        (field (name "PUBLISHER") "Altium Limited")
      )
      (libsource (lib "HabLib") (part "CDERA00275_8"))
    )
    (comp (ref "R34")
      (value "300K")
      (footprint "HABLIB:3216[1206]")
      (description "RESISTOR, CHIP 1206 300K OHM 1% 1/4W THICK FILM ROHS")
      (fields
        (field (name "MFG") "PANASONIC")
        (field (name "TOLERANCE") "1%")
        (field (name "POWER") ".25W")
        (field (name "Comment") "CDERA00275_8")
        (field (name "PUBLISHER") "Altium Limited")
      )
      (libsource (lib "HabLib") (part "CDERA00275_8"))
    )
    (comp (ref "R35")
      (value "10K")
      (footprint "HabLib:3216[1206]")
      (description "RESISTOR, CHIP 1206 10K OHM 1% 1/4W THICK FILM ROHS")
      (fields
        (field (name "MFG") "PANASONIC")
        (field (name "TOLERANCE") "1%")
        (field (name "POWER") ".25W")
        (field (name "Comment") "CDERA00170")
        (field (name "PUBLISHER") "Altium Limited")
      )
      (libsource (lib "HabLib") (part "CDERA00170"))
    )
    (comp (ref "R36")
      (value "300K")
      (footprint "HABLIB:3216[1206]")
      (description "RESISTOR, CHIP 1206 300K OHM 1% 1/4W THICK FILM ROHS")
      (fields
        (field (name "MFG") "PANASONIC")
        (field (name "TOLERANCE") "1%")
        (field (name "POWER") ".25W")
        (field (name "Comment") "CDERA00275_8")
        (field (name "PUBLISHER") "Altium Limited")
      )
      (libsource (lib "HabLib") (part "CDERA00275_8"))
    )
    (comp (ref "R37")
      (value "147K")
      (footprint "3216[1206]")
      (description "RESISTOR, CHIP 1206 147K OHM 1% 1/4W THICK FILM ROHS")
      (fields
        (field (name "MFG") "PANASONIC")
        (field (name "TOLERANCE") "1%")
        (field (name "POWER") ".25W")
        (field (name "Comment") "CDERA00276_2")
      )
      (libsource (lib "HabLib") (part "CDERA00276_2"))
    )
    (comp (ref "R38")
      (value "220")
      (footprint "HABLIB:3216[1206]")
      (description "RESISTOR, CHIP 1206 220 OHM 1% 1/4W THICK FILM ROHS")
      (fields
        (field (name "MFG") "PANASONIC")
        (field (name "TOLERANCE") "1%")
        (field (name "POWER") ".25W")
        (field (name "Comment") "CDERA00273_2")
        (field (name "PUBLISHER") "Altium Limited")
      )
      (libsource (lib "HabLib") (part "CDERA00273_2"))
    )
    (comp (ref "R39")
      (value "100K")
      (footprint "HABLIB:3216[1206]")
      (description "RESISTOR, CHIP 1206 100K OHM 1% 1/4W THICK FILM ROHS")
      (fields
        (field (name "MFG") "PANASONIC")
        (field (name "TOLERANCE") "1%")
        (field (name "POWER") ".25W")
        (field (name "Comment") "CDERA00198")
        (field (name "PUBLISHER") "Altium Limited")
      )
      (libsource (lib "HabLib") (part "CDERA00198"))
    )
    (comp (ref "R40")
      (value "10K")
      (footprint "HabLib:3216[1206]")
      (description "RESISTOR, CHIP 1206 10K OHM 1% 1/4W THICK FILM ROHS")
      (fields
        (field (name "MFG") "PANASONIC")
        (field (name "TOLERANCE") "1%")
        (field (name "POWER") ".25W")
        (field (name "Comment") "CDERA00170")
        (field (name "PUBLISHER") "Altium Limited")
      )
      (libsource (lib "HabLib") (part "CDERA00170"))
    )
    (comp (ref "R41")
      (value "11K")
      (footprint "HABLIB:3216[1206]")
      (description "RESISTOR, CHIP 1206 11K OHM 1% 1/4W THICK FILM ROHS")
      (fields
        (field (name "MFG") "PANASONIC")
        (field (name "TOLERANCE") "1%")
        (field (name "POWER") ".25W")
        (field (name "Comment") "CDERA00275_2")
        (field (name "PUBLISHER") "Altium Limited")
      )
      (libsource (lib "HabLib") (part "CDERA00275_2"))
    )
    (comp (ref "R42")
      (value "59K")
      (footprint "HABLIB:3216[1206]")
      (description "RESISTOR, CHIP 1206 59K OHM 1% 1/4W THICK FILM ROHS")
      (fields
        (field (name "MFG") "PANASONIC")
        (field (name "TOLERANCE") "1%")
        (field (name "POWER") ".25W")
        (field (name "Comment") "CDERA00275_7")
        (field (name "PUBLISHER") "Altium Limited")
      )
      (libsource (lib "HabLib") (part "CDERA00275_7"))
    )
    (comp (ref "R43")
      (value "100K")
      (footprint "HABLIB:3216[1206]")
      (description "RESISTOR, CHIP 1206 100K OHM 1% 1/4W THICK FILM ROHS")
      (fields
        (field (name "MFG") "PANASONIC")
        (field (name "TOLERANCE") "1%")
        (field (name "POWER") ".25W")
        (field (name "Comment") "CDERA00198")
        (field (name "PUBLISHER") "Altium Limited")
      )
      (libsource (lib "HabLib") (part "CDERA00198"))
    )
    (comp (ref "R44")
      (value "300K")
      (footprint "HABLIB:3216[1206]")
      (description "RESISTOR, CHIP 1206 300K OHM 1% 1/4W THICK FILM ROHS")
      (fields
        (field (name "MFG") "PANASONIC")
        (field (name "TOLERANCE") "1%")
        (field (name "POWER") ".25W")
        (field (name "Comment") "CDERA00275_8")
        (field (name "PUBLISHER") "Altium Limited")
      )
      (libsource (lib "HabLib") (part "CDERA00275_8"))
    )
    (comp (ref "R45")
      (value "10K")
      (footprint "HabLib:3216[1206]")
      (description "RESISTOR, CHIP 1206 10K OHM 1% 1/4W THICK FILM ROHS")
      (fields
        (field (name "MFG") "PANASONIC")
        (field (name "TOLERANCE") "1%")
        (field (name "POWER") ".25W")
        (field (name "Comment") "CDERA00170")
        (field (name "PUBLISHER") "Altium Limited")
      )
      (libsource (lib "HabLib") (part "CDERA00170"))
    )
    (comp (ref "R46")
      (value "3.01K")
      (footprint "3216[1206]")
      (description "RESISTOR, CHIP 1206 3.01K OHM 1% 1/4W THICK FILM ROHS")
      (fields
        (field (name "MFG") "PANASONIC")
        (field (name "TOLERANCE") "1%")
        (field (name "POWER") ".25W")
        (field (name "Comment") "CDERA00276_3")
      )
      (libsource (lib "HabLib") (part "CDERA00276_3"))
    )
    (comp (ref "R47")
      (value "30K")
      (footprint "HABLIB:3216[1206]")
      (description "RESISTOR, CHIP 1206 30K OHM 1% 1/4W THICK FILM ROHS")
      (fields
        (field (name "MFG") "PANASONIC")
        (field (name "TOLERANCE") "1%")
        (field (name "POWER") ".25W")
        (field (name "Comment") "CDERA00275_4")
        (field (name "PUBLISHER") "Altium Limited")
      )
      (libsource (lib "HabLib") (part "CDERA00275_4"))
    )
    (comp (ref "R48")
      (value "12K")
      (footprint "HABLIB:3216[1206]")
      (description "RESISTOR, CHIP 1206 12K OHM 1% 1/4W THICK FILM ROHS")
      (fields
        (field (name "MFG") "PANASONIC")
        (field (name "TOLERANCE") "1%")
        (field (name "POWER") ".25W")
        (field (name "Comment") "CDERA00275_5")
        (field (name "PUBLISHER") "Altium Limited")
      )
      (libsource (lib "HabLib") (part "CDERA00275_5"))
    )
    (comp (ref "R49")
      (value "7.5K")
      (footprint "HABLIB:3216[1206]")
      (description "RESISTOR, CHIP 1206 7.5K OHM 1% 1/4W THICK FILM ROHS")
      (fields
        (field (name "MFG") "PANASONIC")
        (field (name "TOLERANCE") "1%")
        (field (name "POWER") ".25W")
        (field (name "Comment") "CDERA00275_3")
        (field (name "PUBLISHER") "Altium Limited")
      )
      (libsource (lib "HabLib") (part "CDERA00275_3"))
    )
    (comp (ref "R50")
      (value "0")
      (footprint "HABLIB:3216[1206]")
      (description "RESISTOR, CHIP 1206 0.0 OHM 1% 1/4W THICK FILM ROHS")
      (fields
        (field (name "MFG") "PANASONIC")
        (field (name "TOLERANCE") "1%")
        (field (name "POWER") ".25W")
        (field (name "Comment") "CDERA00181")
        (field (name "PUBLISHER") "Altium Limited")
      )
      (libsource (lib "HabLib") (part "CDERA00181"))
    )
    (comp (ref "R51")
      (value "0")
      (footprint "HABLIB:3216[1206]")
      (description "RESISTOR, CHIP 1206 0.0 OHM 1% 1/4W THICK FILM ROHS")
      (fields
        (field (name "MFG") "PANASONIC")
        (field (name "TOLERANCE") "1%")
        (field (name "POWER") ".25W")
        (field (name "Comment") "CDERA00181")
        (field (name "PUBLISHER") "Altium Limited")
      )
      (libsource (lib "HabLib") (part "CDERA00181"))
    )
    (comp (ref "R52")
      (value "357")
      (footprint "HABLIB:3216[1206]")
      (description "RESISTOR, CHIP 1206 357 OHM 1% 1/4W THICK FILM ROHS")
      (fields
        (field (name "MFG") "PANASONIC")
        (field (name "TOLERANCE") "1%")
        (field (name "POWER") ".25W")
        (field (name "Comment") "CDERA00275_6")
        (field (name "PUBLISHER") "Altium Limited")
      )
      (libsource (lib "HabLib") (part "CDERA00275_6"))
    )
    (comp (ref "R53")
      (value "270")
      (footprint "HABLIB:3216[1206]")
      (description "RESISTOR, CHIP 1206 270 OHM 1% 1/4W THICK FILM ROHS")
      (fields
        (field (name "MFG") "PANASONIC")
        (field (name "TOLERANCE") "1%")
        (field (name "POWER") ".25W")
        (field (name "Comment") "CDERA00209")
        (field (name "PUBLISHER") "Altium Limited")
      )
      (libsource (lib "HabLib") (part "CDERA00209"))
    )
    (comp (ref "R54")
      (value "100K")
      (footprint "HABLIB:3216[1206]")
      (description "RESISTOR, CHIP 1206 100K OHM 1% 1/4W THICK FILM ROHS")
      (fields
        (field (name "MFG") "PANASONIC")
        (field (name "TOLERANCE") "1%")
        (field (name "POWER") ".25W")
        (field (name "Comment") "CDERA00198")
        (field (name "PUBLISHER") "Altium Limited")
      )
      (libsource (lib "HabLib") (part "CDERA00198"))
    )
    (comp (ref "R55")
      (value "1K")
      (footprint "HABLIB:3216[1206]")
      (description "RESISTOR, CHIP 1206 1K OHM 1% 1/4W THICK FILM ROHS")
      (fields
        (field (name "MFG") "PANASONIC")
        (field (name "TOLERANCE") "1%")
        (field (name "POWER") ".25W")
        (field (name "Comment") "CDERA00195")
        (field (name "PUBLISHER") "Altium Limited")
      )
      (libsource (lib "HabLib") (part "CDERA00195"))
    )
    (comp (ref "R56")
      (value "300K")
      (footprint "HABLIB:3216[1206]")
      (description "RESISTOR, CHIP 1206 300K OHM 1% 1/4W THICK FILM ROHS")
      (fields
        (field (name "MFG") "PANASONIC")
        (field (name "TOLERANCE") "1%")
        (field (name "POWER") ".25W")
        (field (name "Comment") "CDERA00275_8")
        (field (name "PUBLISHER") "Altium Limited")
      )
      (libsource (lib "HabLib") (part "CDERA00275_8"))
    )
    (comp (ref "SW3")
      (value "CDESA00095_1")
      (footprint "COPAL_CSS-1210MC")
      (description "SWITCH, SPST, SLIDE, TH")
      (fields (field (name "MFG") "COPAL ELECTRONICS") (field (name "MFG_PN") "CSS-1210MC"))
      (libsource (lib "HabLib") (part "CDESA00095_1"))
    )
    (comp (ref "U7")
      (value "STMPE24M31")
      (footprint "QFN40P500X500X80-41V_MODIFIED")
      (description "IC, TOUCHKEY CONTROLLER, 24CH, I2C, 40QFN")
      (fields
        (field (name "MFG") "ST")
        (field (name "Comment") "CDEUA00052_1")
        (field (name "PUBLISHER") "Altium Limited")
      )
      (libsource (lib "HabLib") (part "CDEUA00052_1"))
    )
    (comp (ref "U8")
      (value "STMPE24M31")
      (footprint "QFN40P500X500X80-41V_MODIFIED")
      (description "IC, TOUCHKEY CONTROLLER, 24CH, I2C, 40QFN")
      (fields
        (field (name "MFG") "ST")
        (field (name "Comment") "CDEUA00052_1")
        (field (name "PUBLISHER") "Altium Limited")
      )
      (libsource (lib "HabLib") (part "CDEUA00052_1"))
    )
    (comp (ref "U9")
      (value "LM2842X")
      (footprint "TSOT6")
      (description "IC, BUCK REGULATOR, 0.6A, TSOT23-6")
      (fields (field (name "MFG") "NATIONAL SEMICONDUCTOR") (field (name "Comment") "CDEUA00014_1"))
      (libsource (lib "HabLib") (part "CDEUA00014_1"))
    )
  )
  (nets
    (net (code "1") (name "/ACAP0") (class "Default")
      (node (ref "CS37") (pin "1") (pinfunction "1_1") (pintype "passive"))
      (node (ref "U7") (pin "1") (pinfunction "CAP0_1") (pintype "passive"))
    )
    (net (code "2") (name "/ACAP1") (class "Default")
      (node (ref "CS27") (pin "1") (pinfunction "1_1") (pintype "passive"))
      (node (ref "U7") (pin "2") (pinfunction "CAP1_2") (pintype "passive"))
    )
    (net (code "3") (name "/ACAP2") (class "Default")
      (node (ref "CS26") (pin "1") (pinfunction "1_1") (pintype "passive"))
      (node (ref "U7") (pin "3") (pinfunction "CAP2_3") (pintype "passive"))
    )
    (net (code "4") (name "/ACAP3") (class "Default")
      (node (ref "CS14") (pin "1") (pinfunction "1_1") (pintype "passive"))
      (node (ref "U7") (pin "8") (pinfunction "CAP3_8") (pintype "passive"))
    )
    (net (code "5") (name "/ACAP4") (class "Default")
      (node (ref "CS15") (pin "1") (pinfunction "1_1") (pintype "passive"))
      (node (ref "U7") (pin "9") (pinfunction "CAP4_9") (pintype "passive"))
    )
    (net (code "6") (name "/ACAP5") (class "Default")
      (node (ref "CS1") (pin "1") (pinfunction "1_1") (pintype "passive"))
      (node (ref "U7") (pin "10") (pinfunction "CAP5_10") (pintype "passive"))
    )
    (net (code "7") (name "/ACAP6") (class "Default")
      (node (ref "CS2") (pin "1") (pinfunction "1_1") (pintype "passive"))
      (node (ref "U7") (pin "11") (pinfunction "CAP6_11") (pintype "passive"))
    )
    (net (code "8") (name "/ACAP7") (class "Default")
      (node (ref "CS3") (pin "1") (pinfunction "1_1") (pintype "passive"))
      (node (ref "U7") (pin "12") (pinfunction "CAP7_12") (pintype "passive"))
    )
    (net (code "9") (name "/ACAP8") (class "Default")
      (node (ref "CS17") (pin "1") (pinfunction "1_1") (pintype "passive"))
      (node (ref "U7") (pin "28") (pinfunction "CAP8_28") (pintype "passive"))
    )
    (net (code "10") (name "/ACAP9") (class "Default")
      (node (ref "CS18") (pin "1") (pinfunction "1_1") (pintype "passive"))
      (node (ref "U7") (pin "29") (pinfunction "CAP9_29") (pintype "passive"))
    )
    (net (code "11") (name "/ACAP10") (class "Default")
      (node (ref "CS30") (pin "1") (pinfunction "1_1") (pintype "passive"))
      (node (ref "U7") (pin "31") (pinfunction "CAP10_31") (pintype "passive"))
    )
    (net (code "12") (name "/ACAP11") (class "Default")
      (node (ref "CS29") (pin "1") (pinfunction "1_1") (pintype "passive"))
      (node (ref "U7") (pin "32") (pinfunction "CAP11_32") (pintype "passive"))
    )
    (net (code "13") (name "/ACAP12") (class "Default")
      (node (ref "CS28") (pin "1") (pinfunction "1_1") (pintype "passive"))
      (node (ref "U7") (pin "33") (pinfunction "CAP12_33") (pintype "passive"))
    )
    (net (code "14") (name "/ACAP13") (class "Default")
      (node (ref "CS42") (pin "1") (pinfunction "1_1") (pintype "passive"))
      (node (ref "U7") (pin "34") (pinfunction "CAP13_34") (pintype "passive"))
    )
    (net (code "15") (name "/ACAP14") (class "Default")
      (node (ref "CS39") (pin "1") (pinfunction "1_1") (pintype "passive"))
      (node (ref "U7") (pin "39") (pinfunction "CAP14_39") (pintype "passive"))
    )
    (net (code "16") (name "/ACAP15") (class "Default")
      (node (ref "CS38") (pin "1") (pinfunction "1_1") (pintype "passive"))
      (node (ref "U7") (pin "40") (pinfunction "CAP15_40") (pintype "passive"))
    )
    (net (code "17") (name "/ACAP16") (class "Default")
      (node (ref "CS25") (pin "1") (pinfunction "1_1") (pintype "passive"))
      (node (ref "U7") (pin "6") (pinfunction "CAP16_6") (pintype "passive"))
    )
    (net (code "18") (name "/ACAP17") (class "Default")
      (node (ref "CS13") (pin "1") (pinfunction "1_1") (pintype "passive"))
      (node (ref "U7") (pin "7") (pinfunction "CAP17_7") (pintype "passive"))
    )
    (net (code "19") (name "/ACAP18") (class "Default")
      (node (ref "CS4") (pin "1") (pinfunction "1_1") (pintype "passive"))
      (node (ref "U7") (pin "15") (pinfunction "CAP18_15") (pintype "passive"))
    )
    (net (code "20") (name "/ACAP19") (class "Default")
      (node (ref "CS5") (pin "1") (pinfunction "1_1") (pintype "passive"))
      (node (ref "U7") (pin "16") (pinfunction "CAP19_16") (pintype "passive"))
    )
    (net (code "21") (name "/ACAP20") (class "Default")
      (node (ref "CS6") (pin "1") (pinfunction "1_1") (pintype "passive"))
      (node (ref "U7") (pin "25") (pinfunction "CAP20_25") (pintype "passive"))
    )
    (net (code "22") (name "/ACAP21") (class "Default")
      (node (ref "CS16") (pin "1") (pinfunction "1_1") (pintype "passive"))
      (node (ref "U7") (pin "26") (pinfunction "CAP21_26") (pintype "passive"))
    )
    (net (code "23") (name "/ACAP22") (class "Default")
      (node (ref "CS41") (pin "1") (pinfunction "1_1") (pintype "passive"))
      (node (ref "U7") (pin "37") (pinfunction "CPA22_37") (pintype "passive"))
    )
    (net (code "24") (name "/ACAP23") (class "Default")
      (node (ref "CS40") (pin "1") (pinfunction "1_1") (pintype "passive"))
      (node (ref "U7") (pin "38") (pinfunction "CAP23_38") (pintype "passive"))
    )
    (net (code "25") (name "/ADC_BAT") (class "Default")
      (node (ref "C40") (pin "1") (pinfunction "1_1") (pintype "passive"))
      (node (ref "R37") (pin "1") (pinfunction "1_1") (pintype "passive"))
      (node (ref "R39") (pin "2") (pinfunction "2_2") (pintype "passive"))
    )
    (net (code "26") (name "/ADC_METER") (class "Default")
      (node (ref "C44") (pin "1") (pinfunction "1_1") (pintype "passive"))
      (node (ref "D19") (pin "1") (pinfunction "A_1") (pintype "passive"))
      (node (ref "D21") (pin "2") (pinfunction "K_2") (pintype "passive"))
      (node (ref "R31") (pin "2") (pinfunction "2_2") (pintype "passive"))
      (node (ref "R42") (pin "2") (pinfunction "2_2") (pintype "passive"))
      (node (ref "R47") (pin "2") (pinfunction "2_2") (pintype "passive"))
      (node (ref "R48") (pin "2") (pinfunction "2_2") (pintype "passive"))
      (node (ref "R49") (pin "2") (pinfunction "2_2") (pintype "passive"))
    )
    (net (code "27") (name "/BAT_CON") (class "Default")
      (node (ref "Q18") (pin "1") (pinfunction "B_1") (pintype "passive"))
      (node (ref "Q4") (pin "1") (pinfunction "B_1") (pintype "passive"))
      (node (ref "Q5") (pin "1") (pinfunction "B_1") (pintype "passive"))
      (node (ref "Q9") (pin "3") (pinfunction "C_3") (pintype "passive"))
      (node (ref "R44") (pin "1") (pinfunction "1_1") (pintype "passive"))
    )
    (net (code "28") (name "/BCAP0") (class "Default")
      (node (ref "CS34") (pin "1") (pinfunction "1_1") (pintype "passive"))
      (node (ref "U8") (pin "1") (pinfunction "CAP0_1") (pintype "passive"))
    )
    (net (code "29") (name "/BCAP1") (class "Default")
      (node (ref "CS35") (pin "1") (pinfunction "1_1") (pintype "passive"))
      (node (ref "U8") (pin "2") (pinfunction "CAP1_2") (pintype "passive"))
    )
    (net (code "30") (name "/BCAP2") (class "Default")
      (node (ref "CS47") (pin "1") (pinfunction "1_1") (pintype "passive"))
      (node (ref "U8") (pin "3") (pinfunction "CAP2_3") (pintype "passive"))
    )
    (net (code "31") (name "/BCAP3") (class "Default")
      (node (ref "CS44") (pin "1") (pinfunction "1_1") (pintype "passive"))
      (node (ref "U8") (pin "8") (pinfunction "CAP3_8") (pintype "passive"))
    )
    (net (code "32") (name "/BCAP4") (class "Default")
      (node (ref "CS32") (pin "1") (pinfunction "1_1") (pintype "passive"))
      (node (ref "U8") (pin "9") (pinfunction "CAP4_9") (pintype "passive"))
    )
    (net (code "33") (name "/BCAP5") (class "Default")
      (node (ref "CS43") (pin "1") (pinfunction "1_1") (pintype "passive"))
      (node (ref "U8") (pin "10") (pinfunction "CAP5_10") (pintype "passive"))
    )
    (net (code "34") (name "/BCAP6") (class "Default")
      (node (ref "CS19") (pin "1") (pinfunction "1_1") (pintype "passive"))
      (node (ref "U8") (pin "11") (pinfunction "CAP6_11") (pintype "passive"))
    )
    (net (code "35") (name "/BCAP7") (class "Default")
      (node (ref "CS20") (pin "1") (pinfunction "1_1") (pintype "passive"))
      (node (ref "U8") (pin "12") (pinfunction "CAP7_12") (pintype "passive"))
    )
    (net (code "36") (name "/BCAP8") (class "Default")
      (node (ref "CS31") (pin "1") (pinfunction "1_1") (pintype "passive"))
      (node (ref "U8") (pin "28") (pinfunction "CAP8_28") (pintype "passive"))
    )
    (net (code "37") (name "/BCAP9") (class "Default")
      (node (ref "CS36") (pin "1") (pinfunction "1_1") (pintype "passive"))
      (node (ref "U8") (pin "29") (pinfunction "CAP9_29") (pintype "passive"))
    )
    (net (code "38") (name "/BCAP10") (class "Default")
      (node (ref "CS48") (pin "1") (pinfunction "1_1") (pintype "passive"))
      (node (ref "U8") (pin "31") (pinfunction "CAP10_31") (pintype "passive"))
    )
    (net (code "39") (name "/BCAP11") (class "Default")
      (node (ref "CS9") (pin "1") (pinfunction "1_1") (pintype "passive"))
      (node (ref "U8") (pin "32") (pinfunction "CAP11_32") (pintype "passive"))
    )
    (net (code "40") (name "/BCAP12") (class "Default")
      (node (ref "CS10") (pin "1") (pinfunction "1_1") (pintype "passive"))
      (node (ref "U8") (pin "33") (pinfunction "CAP12_33") (pintype "passive"))
    )
    (net (code "41") (name "/BCAP13") (class "Default")
      (node (ref "CS11") (pin "1") (pinfunction "1_1") (pintype "passive"))
      (node (ref "U8") (pin "34") (pinfunction "CAP13_34") (pintype "passive"))
    )
    (net (code "42") (name "/BCAP14") (class "Default")
      (node (ref "CS23") (pin "1") (pinfunction "1_1") (pintype "passive"))
      (node (ref "U8") (pin "39") (pinfunction "CAP14_39") (pintype "passive"))
    )
    (net (code "43") (name "/BCAP15") (class "Default")
      (node (ref "CS33") (pin "1") (pinfunction "1_1") (pintype "passive"))
      (node (ref "U8") (pin "40") (pinfunction "CAP15_40") (pintype "passive"))
    )
    (net (code "44") (name "/BCAP16") (class "Default")
      (node (ref "CS46") (pin "1") (pinfunction "1_1") (pintype "passive"))
      (node (ref "U8") (pin "6") (pinfunction "CAP16_6") (pintype "passive"))
    )
    (net (code "45") (name "/BCAP17") (class "Default")
      (node (ref "CS45") (pin "1") (pinfunction "1_1") (pintype "passive"))
      (node (ref "U8") (pin "7") (pinfunction "CAP17_7") (pintype "passive"))
    )
    (net (code "46") (name "/BCAP18") (class "Default")
      (node (ref "CS7") (pin "1") (pinfunction "1_1") (pintype "passive"))
      (node (ref "U8") (pin "15") (pinfunction "CAP18_15") (pintype "passive"))
    )
    (net (code "47") (name "/BCAP19") (class "Default")
      (node (ref "CS8") (pin "1") (pinfunction "1_1") (pintype "passive"))
      (node (ref "U8") (pin "16") (pinfunction "CAP19_16") (pintype "passive"))
    )
    (net (code "48") (name "/BCAP20") (class "Default")
      (node (ref "CS12") (pin "1") (pinfunction "1_1") (pintype "passive"))
      (node (ref "U8") (pin "25") (pinfunction "CAP20_25") (pintype "passive"))
    )
    (net (code "49") (name "/BCAP21") (class "Default")
      (node (ref "CS24") (pin "1") (pinfunction "1_1") (pintype "passive"))
      (node (ref "U8") (pin "26") (pinfunction "CAP21_26") (pintype "passive"))
    )
    (net (code "50") (name "/BCAP22") (class "Default")
      (node (ref "CS21") (pin "1") (pinfunction "1_1") (pintype "passive"))
      (node (ref "U8") (pin "37") (pinfunction "CPA22_37") (pintype "passive"))
    )
    (net (code "51") (name "/BCAP23") (class "Default")
      (node (ref "CS22") (pin "1") (pinfunction "1_1") (pintype "passive"))
      (node (ref "U8") (pin "38") (pinfunction "CAP23_38") (pintype "passive"))
    )
    (net (code "52") (name "/INT_ACAP") (class "Default")
      (node (ref "R29") (pin "1") (pinfunction "1_1") (pintype "passive"))
      (node (ref "U7") (pin "18") (pinfunction "INT_18") (pintype "passive"))
    )
    (net (code "53") (name "/INT_BCAP") (class "Default")
      (node (ref "R30") (pin "1") (pinfunction "1_1") (pintype "passive"))
      (node (ref "U8") (pin "18") (pinfunction "INT_18") (pintype "passive"))
    )
    (net (code "54") (name "/PWM_BL") (class "Default")
      (node (ref "Q6") (pin "1") (pinfunction "B_1") (pintype "passive"))
    )
    (net (code "55") (name "/RNG_10") (class "Default")
      (node (ref "Q11") (pin "1") (pinfunction "B_1") (pintype "passive"))
    )
    (net (code "56") (name "/RNG_20") (class "Default")
      (node (ref "Q12") (pin "1") (pinfunction "B_1") (pintype "passive"))
    )
    (net (code "57") (name "/RNG_30") (class "Default")
      (node (ref "Q13") (pin "1") (pinfunction "B_1") (pintype "passive"))
    )
    (net (code "58") (name "/SCL0") (class "Default")
      (node (ref "U7") (pin "20") (pinfunction "SCL_20") (pintype "passive"))
      (node (ref "U8") (pin "20") (pinfunction "SCL_20") (pintype "passive"))
    )
    (net (code "59") (name "/SDA0") (class "Default")
      (node (ref "U7") (pin "21") (pinfunction "SDA_21") (pintype "passive"))
      (node (ref "U8") (pin "21") (pinfunction "SDA_21") (pintype "passive"))
    )
    (net (code "60") (name "/SEL_V{slash}~{C}") (class "Default")
      (node (ref "Q16") (pin "1") (pinfunction "B_1") (pintype "passive"))
      (node (ref "Q8") (pin "1") (pinfunction "B_1") (pintype "passive"))
      (node (ref "R56") (pin "1") (pinfunction "1_1") (pintype "passive"))
    )
    (net (code "61") (name "/SYS_RST") (class "Default")
      (node (ref "U7") (pin "22") (pinfunction "RST_22") (pintype "passive"))
      (node (ref "U8") (pin "22") (pinfunction "RST_22") (pintype "passive"))
    )
    (net (code "62") (name "/VREF30") (class "Default")
      (node (ref "Q10") (pin "2") (pinfunction "E_2") (pintype "passive"))
      (node (ref "R54") (pin "2") (pinfunction "2_2") (pintype "passive"))
    )
    (net (code "63") (name "3.3V") (class "Default")
      (node (ref "C29") (pin "1") (pinfunction "1_1") (pintype "passive"))
      (node (ref "C30") (pin "1") (pinfunction "1_1") (pintype "passive"))
      (node (ref "C31") (pin "1") (pinfunction "1_1") (pintype "passive"))
      (node (ref "C32") (pin "1") (pinfunction "1_1") (pintype "passive"))
      (node (ref "C33") (pin "1") (pinfunction "1_1") (pintype "passive"))
      (node (ref "C34") (pin "1") (pinfunction "1_1") (pintype "passive"))
      (node (ref "C35") (pin "1") (pinfunction "1_1") (pintype "passive"))
      (node (ref "C36") (pin "1") (pinfunction "1_1") (pintype "passive"))
      (node (ref "C38") (pin "1") (pinfunction "1_1") (pintype "passive"))
      (node (ref "C39") (pin "1") (pinfunction "1_1") (pintype "passive"))
      (node (ref "D19") (pin "2") (pinfunction "K_2") (pintype "passive"))
      (node (ref "L1") (pin "2") (pinfunction "2_2") (pintype "passive"))
      (node (ref "R29") (pin "2") (pinfunction "2_2") (pintype "passive"))
      (node (ref "R30") (pin "2") (pinfunction "2_2") (pintype "passive"))
      (node (ref "R33") (pin "2") (pinfunction "2_2") (pintype "passive"))
      (node (ref "R40") (pin "2") (pinfunction "2_2") (pintype "passive"))
      (node (ref "R56") (pin "2") (pinfunction "2_2") (pintype "passive"))
      (node (ref "U7") (pin "14") (pinfunction "VIO_14") (pintype "passive"))
      (node (ref "U7") (pin "30") (pinfunction "VIO_30") (pintype "passive"))
      (node (ref "U7") (pin "35") (pinfunction "VIO_35") (pintype "passive"))
      (node (ref "U7") (pin "5") (pinfunction "VIO_5") (pintype "passive"))
      (node (ref "U8") (pin "14") (pinfunction "VIO_14") (pintype "passive"))
      (node (ref "U8") (pin "19") (pinfunction "ADDR0_19") (pintype "passive"))
      (node (ref "U8") (pin "30") (pinfunction "VIO_30") (pintype "passive"))
      (node (ref "U8") (pin "35") (pinfunction "VIO_35") (pintype "passive"))
      (node (ref "U8") (pin "5") (pinfunction "VIO_5") (pintype "passive"))
    )
    (net (code "64") (name "6V") (class "Default")
      (node (ref "Q18") (pin "2") (pinfunction "E_2") (pintype "passive"))
      (node (ref "Q4") (pin "2") (pinfunction "E_2") (pintype "passive"))
      (node (ref "R37") (pin "2") (pinfunction "2_2") (pintype "passive"))
      (node (ref "R43") (pin "2") (pinfunction "2_2") (pintype "passive"))
      (node (ref "R44") (pin "2") (pinfunction "2_2") (pintype "passive"))
      (node (ref "SW3") (pin "3") (pintype "passive"))
    )
    (net (code "65") (name "GND") (class "Default")
      (node (ref "BAT2") (pin "2") (pinfunction "2_2") (pintype "passive"))
      (node (ref "C25") (pin "2") (pinfunction "2_2") (pintype "passive"))
      (node (ref "C26") (pin "2") (pinfunction "2_2") (pintype "passive"))
      (node (ref "C27") (pin "2") (pinfunction "2_2") (pintype "passive"))
      (node (ref "C28") (pin "2") (pinfunction "2_2") (pintype "passive"))
      (node (ref "C29") (pin "2") (pinfunction "2_2") (pintype "passive"))
      (node (ref "C30") (pin "2") (pinfunction "2_2") (pintype "passive"))
      (node (ref "C31") (pin "2") (pinfunction "2_2") (pintype "passive"))
      (node (ref "C32") (pin "2") (pinfunction "2_2") (pintype "passive"))
      (node (ref "C33") (pin "2") (pinfunction "2_2") (pintype "passive"))
      (node (ref "C34") (pin "2") (pinfunction "2_2") (pintype "passive"))
      (node (ref "C35") (pin "2") (pinfunction "2_2") (pintype "passive"))
      (node (ref "C36") (pin "2") (pinfunction "2_2") (pintype "passive"))
      (node (ref "C38") (pin "2") (pinfunction "2_2") (pintype "passive"))
      (node (ref "C39") (pin "2") (pinfunction "2_2") (pintype "passive"))
      (node (ref "C40") (pin "2") (pinfunction "2_2") (pintype "passive"))
      (node (ref "C41") (pin "1") (pinfunction "1_1") (pintype "passive"))
      (node (ref "C42") (pin "2") (pinfunction "2_2") (pintype "passive"))
      (node (ref "C43") (pin "2") (pinfunction "2_2") (pintype "passive"))
      (node (ref "C46") (pin "2") (pinfunction "2_2") (pintype "passive"))
      (node (ref "D18") (pin "1") (pinfunction "A_1") (pintype "passive"))
      (node (ref "FB5") (pin "1") (pinfunction "1_1") (pintype "passive"))
      (node (ref "Q17") (pin "2") (pinfunction "E_2") (pintype "passive"))
      (node (ref "Q6") (pin "2") (pinfunction "E_2") (pintype "passive"))
      (node (ref "Q9") (pin "2") (pinfunction "E_2") (pintype "passive"))
      (node (ref "R39") (pin "1") (pinfunction "1_1") (pintype "passive"))
      (node (ref "R45") (pin "1") (pinfunction "1_1") (pintype "passive"))
      (node (ref "R46") (pin "1") (pinfunction "1_1") (pintype "passive"))
      (node (ref "U7") (pin "13") (pinfunction "GND_13") (pintype "passive"))
      (node (ref "U7") (pin "19") (pinfunction "ADDR0_19") (pintype "passive"))
      (node (ref "U7") (pin "23") (pinfunction "ADDR1_23") (pintype "passive"))
      (node (ref "U7") (pin "27") (pinfunction "GND_27") (pintype "passive"))
      (node (ref "U7") (pin "36") (pinfunction "GND_36") (pintype "passive"))
      (node (ref "U7") (pin "4") (pinfunction "GND_4") (pintype "passive"))
      (node (ref "U8") (pin "13") (pinfunction "GND_13") (pintype "passive"))
      (node (ref "U8") (pin "23") (pinfunction "ADDR1_23") (pintype "passive"))
      (node (ref "U8") (pin "27") (pinfunction "GND_27") (pintype "passive"))
      (node (ref "U8") (pin "36") (pinfunction "GND_36") (pintype "passive"))
      (node (ref "U8") (pin "4") (pinfunction "GND_4") (pintype "passive"))
      (node (ref "U9") (pin "2") (pinfunction "GND_2") (pintype "passive"))
    )
    (net (code "66") (name "GNDA") (class "Default")
      (node (ref "C44") (pin "2") (pinfunction "2_2") (pintype "passive"))
      (node (ref "D21") (pin "1") (pinfunction "A_1") (pintype "passive"))
      (node (ref "FB5") (pin "2") (pinfunction "2_2") (pintype "passive"))
      (node (ref "Q11") (pin "2") (pinfunction "E_2") (pintype "passive"))
      (node (ref "Q12") (pin "2") (pinfunction "E_2") (pintype "passive"))
      (node (ref "Q13") (pin "2") (pinfunction "E_2") (pintype "passive"))
      (node (ref "Q15") (pin "2") (pinfunction "E_2") (pintype "passive"))
      (node (ref "Q16") (pin "2") (pinfunction "E_2") (pintype "passive"))
      (node (ref "Q7") (pin "2") (pinfunction "E_2") (pintype "passive"))
      (node (ref "Q8") (pin "2") (pinfunction "E_2") (pintype "passive"))
    )
    (net (code "67") (name "Net-(BAT1-Pad2)") (class "Default")
      (node (ref "BAT1") (pin "2") (pinfunction "2_2") (pintype "passive"))
      (node (ref "BAT2") (pin "1") (pinfunction "1_1") (pintype "passive"))
    )
    (net (code "68") (name "Net-(D15-A)") (class "Default")
      (node (ref "D15") (pin "1") (pinfunction "A_1") (pintype "passive"))
      (node (ref "Q2") (pin "1") (pinfunction "B_1") (pintype "passive"))
      (node (ref "R34") (pin "2") (pinfunction "2_2") (pintype "passive"))
      (node (ref "R35") (pin "1") (pinfunction "1_1") (pintype "passive"))
    )
    (net (code "69") (name "Net-(D15-K)") (class "Default")
      (node (ref "C45") (pin "1") (pinfunction "1_1") (pintype "passive"))
      (node (ref "D15") (pin "3") (pinfunction "K_3") (pintype "passive"))
      (node (ref "J5") (pin "1") (pinfunction "1_1") (pintype "passive"))
      (node (ref "Q2") (pin "2") (pinfunction "E_2") (pintype "passive"))
      (node (ref "R34") (pin "1") (pinfunction "1_1") (pintype "passive"))
      (node (ref "R41") (pin "1") (pinfunction "1_1") (pintype "passive"))
    )
    (net (code "70") (name "Net-(D16-A)") (class "Default")
      (node (ref "D16") (pin "1") (pinfunction "A_1") (pintype "passive"))
      (node (ref "R32") (pin "1") (pinfunction "1_1") (pintype "passive"))
    )
    (net (code "71") (name "Net-(D16-K)") (class "Default")
      (node (ref "D16") (pin "2") (pinfunction "K_2") (pintype "passive"))
      (node (ref "D17") (pin "2") (pinfunction "K_2") (pintype "passive"))
      (node (ref "Q3") (pin "2") (pinfunction "E_2") (pintype "passive"))
      (node (ref "R36") (pin "2") (pinfunction "2_2") (pintype "passive"))
    )
    (net (code "72") (name "Net-(D17-A)") (class "Default")
      (node (ref "D17") (pin "1") (pinfunction "A_1") (pintype "passive"))
      (node (ref "R38") (pin "2") (pinfunction "2_2") (pintype "passive"))
    )
    (net (code "73") (name "Net-(D18-K)") (class "Default")
      (node (ref "C37") (pin "2") (pinfunction "2_2") (pintype "passive"))
      (node (ref "D18") (pin "2") (pinfunction "K_2") (pintype "passive"))
      (node (ref "L1") (pin "1") (pinfunction "1_1") (pintype "passive"))
      (node (ref "U9") (pin "6") (pinfunction "SW_6") (pintype "passive"))
    )
    (net (code "74") (name "Net-(D20-A)") (class "Default")
      (node (ref "D20") (pin "1") (pinfunction "A_1") (pintype "passive"))
      (node (ref "D22") (pin "1") (pinfunction "A_1") (pintype "passive"))
    )
    (net (code "75") (name "Net-(D20-K)") (class "Default")
      (node (ref "D20") (pin "3") (pinfunction "K_3") (pintype "passive"))
      (node (ref "R41") (pin "2") (pinfunction "2_2") (pintype "passive"))
      (node (ref "R42") (pin "1") (pinfunction "1_1") (pintype "passive"))
    )
    (net (code "76") (name "Net-(D22-K)") (class "Default")
      (node (ref "C45") (pin "2") (pinfunction "2_2") (pintype "passive"))
      (node (ref "D22") (pin "3") (pinfunction "K_3") (pintype "passive"))
      (node (ref "J5") (pin "2") (pinfunction "2_2") (pintype "passive"))
      (node (ref "Q16") (pin "3") (pinfunction "C_3") (pintype "passive"))
      (node (ref "R50") (pin "1") (pinfunction "1_1") (pintype "passive"))
    )
    (net (code "77") (name "Net-(D23-A)") (class "Default")
      (node (ref "D23") (pin "1") (pinfunction "A_1") (pintype "passive"))
      (node (ref "Q14") (pin "2") (pinfunction "E_2") (pintype "passive"))
    )
    (net (code "78") (name "Net-(Q2-C)") (class "Default")
      (node (ref "Q2") (pin "3") (pinfunction "C_3") (pintype "passive"))
      (node (ref "R31") (pin "1") (pinfunction "1_1") (pintype "passive"))
    )
    (net (code "79") (name "Net-(Q3-B)") (class "Default")
      (node (ref "Q3") (pin "1") (pinfunction "B_1") (pintype "passive"))
      (node (ref "Q6") (pin "3") (pinfunction "C_3") (pintype "passive"))
      (node (ref "R36") (pin "1") (pinfunction "1_1") (pintype "passive"))
    )
    (net (code "80") (name "Net-(Q4-C)") (class "Default")
      (node (ref "Q4") (pin "3") (pinfunction "C_3") (pintype "passive"))
      (node (ref "Q5") (pin "3") (pinfunction "C_3") (pintype "passive"))
    )
    (net (code "81") (name "Net-(Q7-C)") (class "Default")
      (node (ref "Q7") (pin "3") (pinfunction "C_3") (pintype "passive"))
      (node (ref "R35") (pin "2") (pinfunction "2_2") (pintype "passive"))
    )
    (net (code "82") (name "Net-(Q10-B)") (class "Default")
      (node (ref "Q10") (pin "1") (pinfunction "B_1") (pintype "passive"))
      (node (ref "R54") (pin "1") (pinfunction "1_1") (pintype "passive"))
      (node (ref "R55") (pin "2") (pinfunction "2_2") (pintype "passive"))
    )
    (net (code "83") (name "Net-(Q10-C)") (class "Default")
      (node (ref "Q10") (pin "3") (pinfunction "C_3") (pintype "passive"))
      (node (ref "R50") (pin "2") (pinfunction "2_2") (pintype "passive"))
    )
    (net (code "84") (name "Net-(Q11-C)") (class "Default")
      (node (ref "Q11") (pin "3") (pinfunction "C_3") (pintype "passive"))
      (node (ref "R51") (pin "1") (pinfunction "1_1") (pintype "passive"))
    )
    (net (code "85") (name "Net-(Q12-C)") (class "Default")
      (node (ref "Q12") (pin "3") (pinfunction "C_3") (pintype "passive"))
      (node (ref "R52") (pin "1") (pinfunction "1_1") (pintype "passive"))
    )
    (net (code "86") (name "Net-(Q13-C)") (class "Default")
      (node (ref "Q13") (pin "3") (pinfunction "C_3") (pintype "passive"))
      (node (ref "R53") (pin "1") (pinfunction "1_1") (pintype "passive"))
    )
    (net (code "87") (name "Net-(Q14-B)") (class "Default")
      (node (ref "C41") (pin "2") (pinfunction "2_2") (pintype "passive"))
      (node (ref "Q14") (pin "1") (pinfunction "B_1") (pintype "passive"))
      (node (ref "Q17") (pin "3") (pinfunction "C_3") (pintype "passive"))
      (node (ref "Q9") (pin "1") (pinfunction "B_1") (pintype "passive"))
      (node (ref "R43") (pin "1") (pinfunction "1_1") (pintype "passive"))
    )
    (net (code "88") (name "Net-(Q15-B)") (class "Default")
      (node (ref "Q15") (pin "1") (pinfunction "B_1") (pintype "passive"))
      (node (ref "Q7") (pin "1") (pinfunction "B_1") (pintype "passive"))
      (node (ref "Q8") (pin "3") (pinfunction "C_3") (pintype "passive"))
      (node (ref "R33") (pin "1") (pinfunction "1_1") (pintype "passive"))
    )
    (net (code "89") (name "Net-(Q15-C)") (class "Default")
      (node (ref "Q15") (pin "3") (pinfunction "C_3") (pintype "passive"))
      (node (ref "R55") (pin "1") (pinfunction "1_1") (pintype "passive"))
    )
    (net (code "90") (name "Net-(Q18-C)") (class "Default")
      (node (ref "Q18") (pin "3") (pinfunction "C_3") (pintype "passive"))
      (node (ref "R32") (pin "2") (pinfunction "2_2") (pintype "passive"))
    )
    (net (code "91") (name "Net-(R47-Pad1)") (class "Default")
      (node (ref "R47") (pin "1") (pinfunction "1_1") (pintype "passive"))
      (node (ref "R51") (pin "2") (pinfunction "2_2") (pintype "passive"))
    )
    (net (code "92") (name "Net-(R48-Pad1)") (class "Default")
      (node (ref "R48") (pin "1") (pinfunction "1_1") (pintype "passive"))
      (node (ref "R52") (pin "2") (pinfunction "2_2") (pintype "passive"))
    )
    (net (code "93") (name "Net-(R49-Pad1)") (class "Default")
      (node (ref "R49") (pin "1") (pinfunction "1_1") (pintype "passive"))
      (node (ref "R53") (pin "2") (pinfunction "2_2") (pintype "passive"))
    )
    (net (code "94") (name "Net-(U7-CREF)") (class "Default")
      (node (ref "C25") (pin "1") (pinfunction "1_1") (pintype "passive"))
      (node (ref "U7") (pin "24") (pinfunction "CREF_24") (pintype "passive"))
    )
    (net (code "95") (name "Net-(U7-VCC)") (class "Default")
      (node (ref "C27") (pin "1") (pinfunction "1_1") (pintype "passive"))
      (node (ref "U7") (pin "17") (pinfunction "VCC_17") (pintype "passive"))
    )
    (net (code "96") (name "Net-(U8-CREF)") (class "Default")
      (node (ref "C26") (pin "1") (pinfunction "1_1") (pintype "passive"))
      (node (ref "U8") (pin "24") (pinfunction "CREF_24") (pintype "passive"))
    )
    (net (code "97") (name "Net-(U8-VCC)") (class "Default")
      (node (ref "C28") (pin "1") (pinfunction "1_1") (pintype "passive"))
      (node (ref "U8") (pin "17") (pinfunction "VCC_17") (pintype "passive"))
    )
    (net (code "98") (name "Net-(U9-CB)") (class "Default")
      (node (ref "C37") (pin "1") (pinfunction "1_1") (pintype "passive"))
      (node (ref "U9") (pin "1") (pinfunction "CB_1") (pintype "passive"))
    )
    (net (code "99") (name "Net-(U9-FB)") (class "Default")
      (node (ref "R40") (pin "1") (pinfunction "1_1") (pintype "passive"))
      (node (ref "R46") (pin "2") (pinfunction "2_2") (pintype "passive"))
      (node (ref "U9") (pin "3") (pinfunction "FB_3") (pintype "passive"))
    )
    (net (code "100") (name "VBL") (class "Default")
      (node (ref "Q3") (pin "3") (pinfunction "C_3") (pintype "passive"))
    )
    (net (code "101") (name "VCC") (class "Default")
      (node (ref "C42") (pin "1") (pinfunction "1_1") (pintype "passive"))
      (node (ref "C43") (pin "1") (pinfunction "1_1") (pintype "passive"))
      (node (ref "D23") (pin "2") (pinfunction "K_2") (pintype "passive"))
      (node (ref "Q5") (pin "2") (pinfunction "E_2") (pintype "passive"))
      (node (ref "U9") (pin "4") (pinfunction "SHDN_4") (pintype "passive"))
      (node (ref "U9") (pin "5") (pinfunction "VIN_5") (pintype "passive"))
    )
    (net (code "102") (name "VCELL") (class "Default")
      (node (ref "BAT1") (pin "1") (pinfunction "1_1") (pintype "passive"))
      (node (ref "SW3") (pin "2") (pintype "passive"))
    )
    (net (code "103") (name "VUSB") (class "Default")
      (node (ref "C46") (pin "1") (pinfunction "1_1") (pintype "passive"))
      (node (ref "Q14") (pin "3") (pinfunction "C_3") (pintype "passive"))
      (node (ref "Q17") (pin "1") (pinfunction "B_1") (pintype "passive"))
      (node (ref "R38") (pin "1") (pinfunction "1_1") (pintype "passive"))
      (node (ref "R45") (pin "2") (pinfunction "2_2") (pintype "passive"))
    )
    (net (code "104") (name "unconnected-(SW3-Pad1)") (class "Default")
      (node (ref "SW3") (pin "1") (pintype "passive"))
    )
  )
)
